# design.net
KiCad netlist of a schematic drawn in Altium Designer
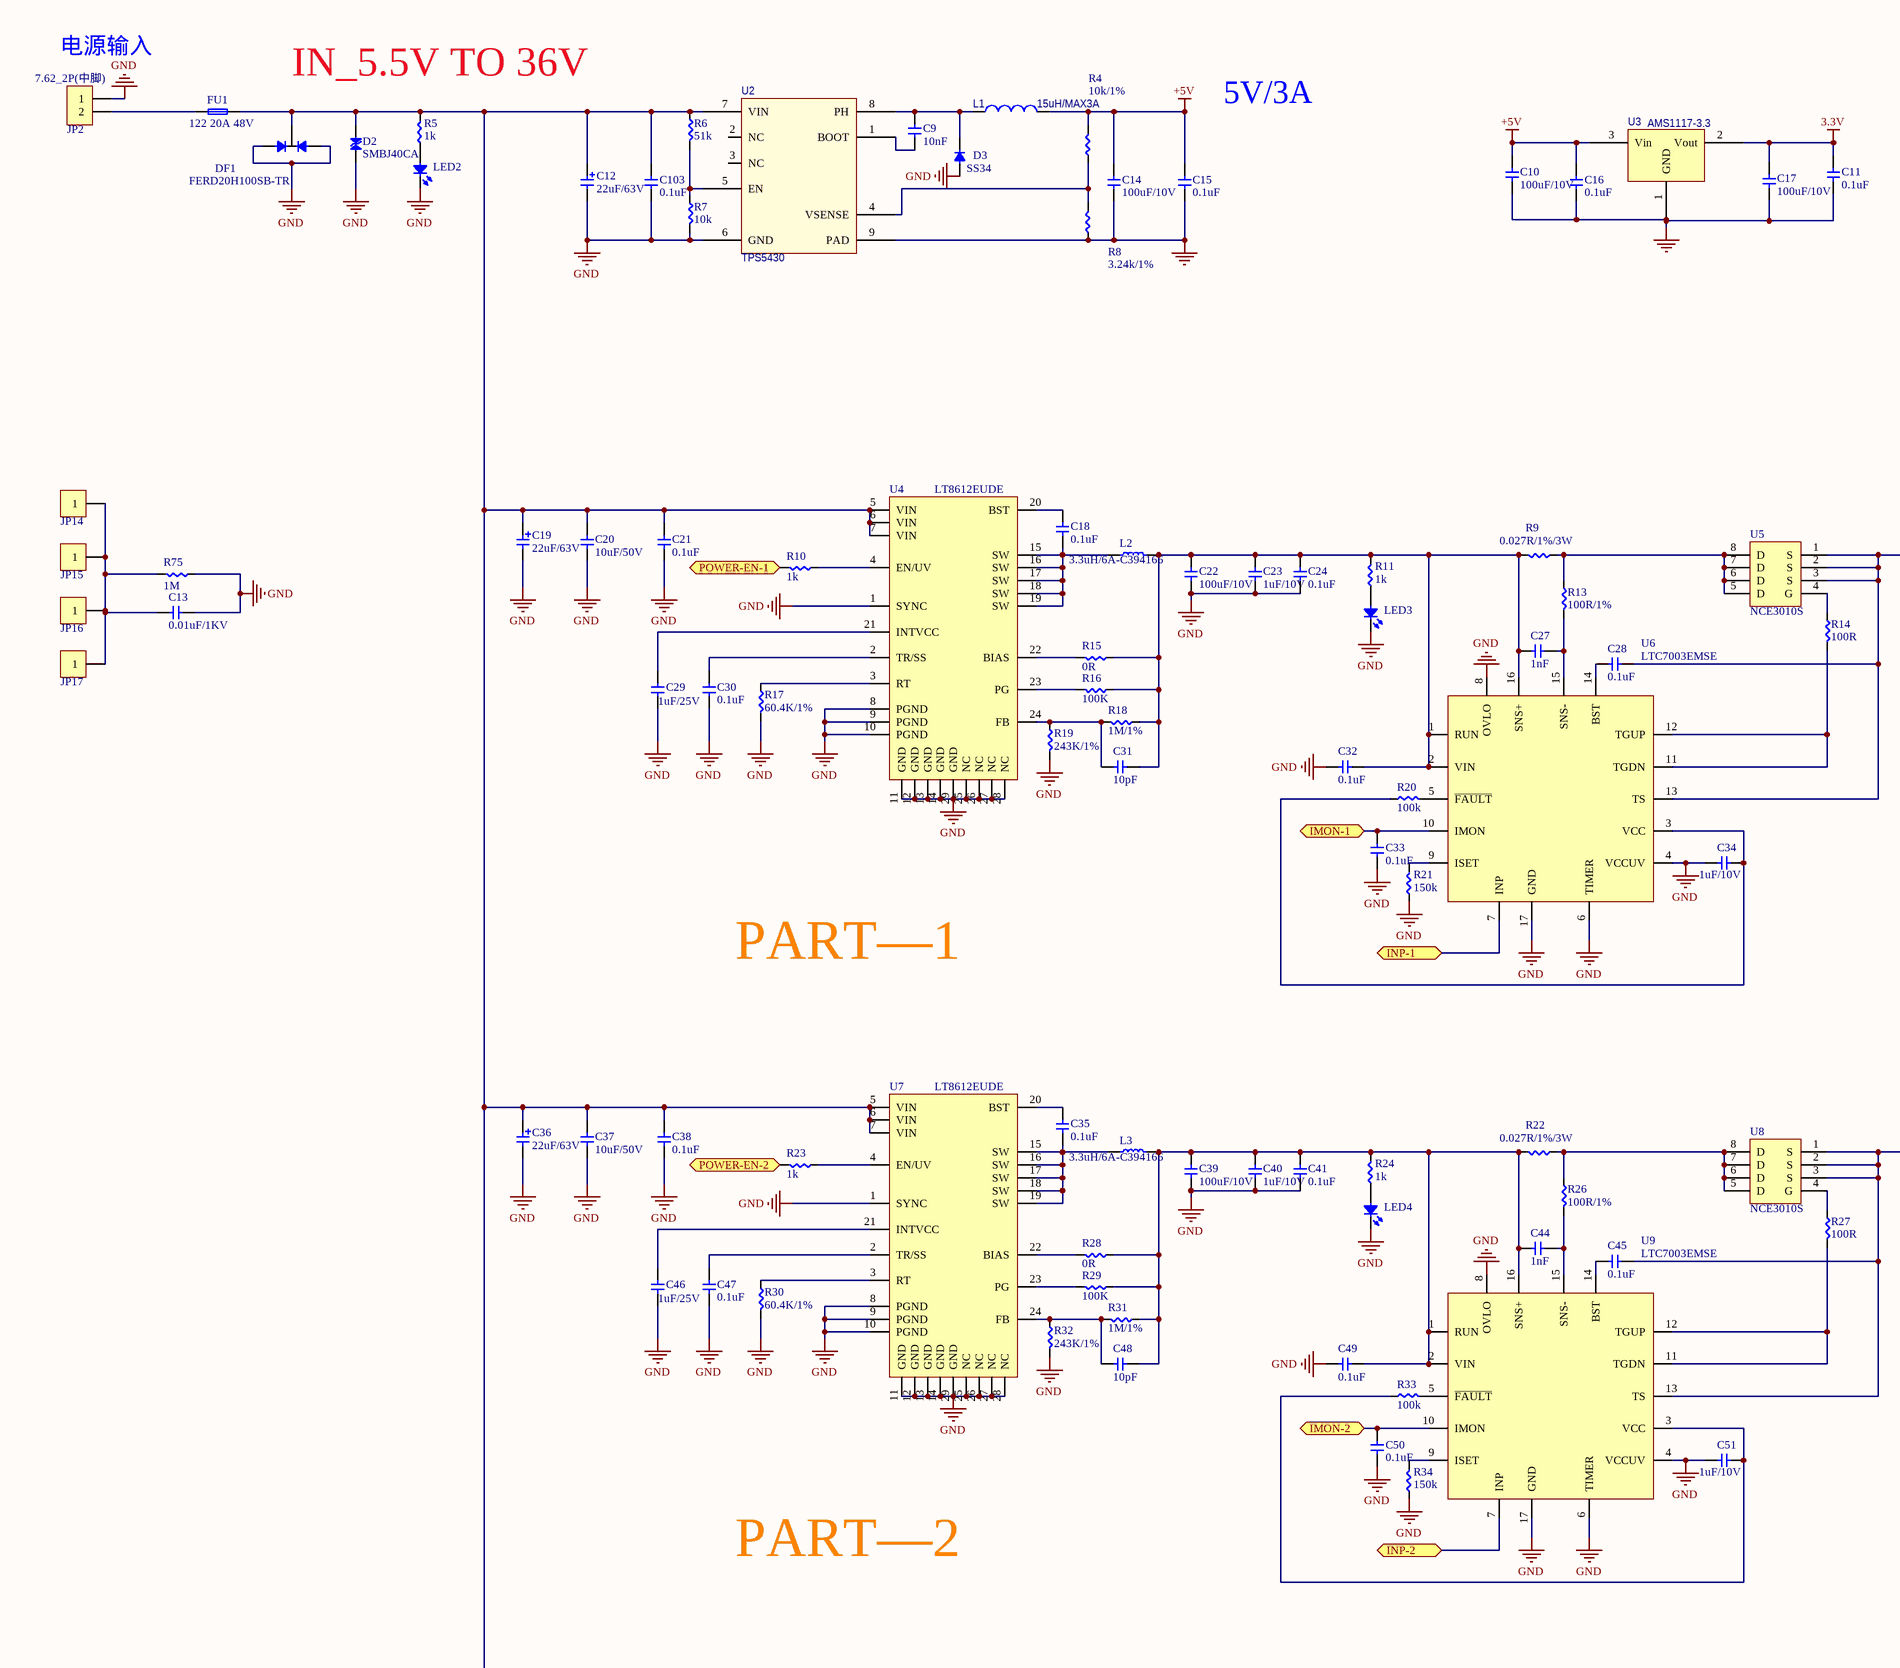
[diagram p0: 电源通道电路.SchDoc, top left]
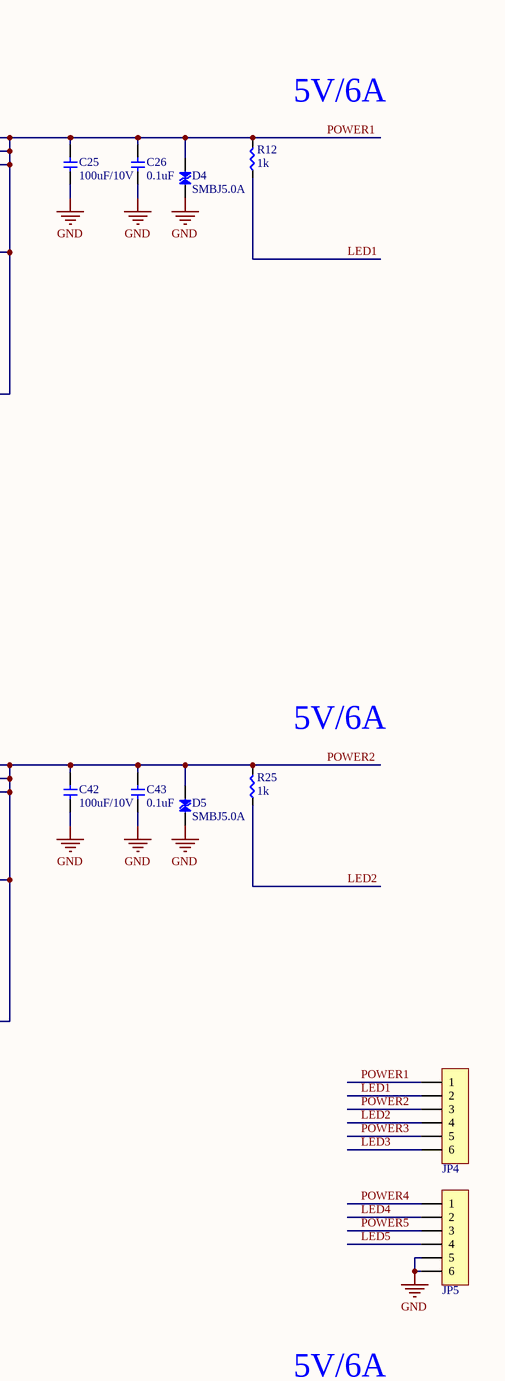
[diagram p1: 电源通道电路.SchDoc, top right]
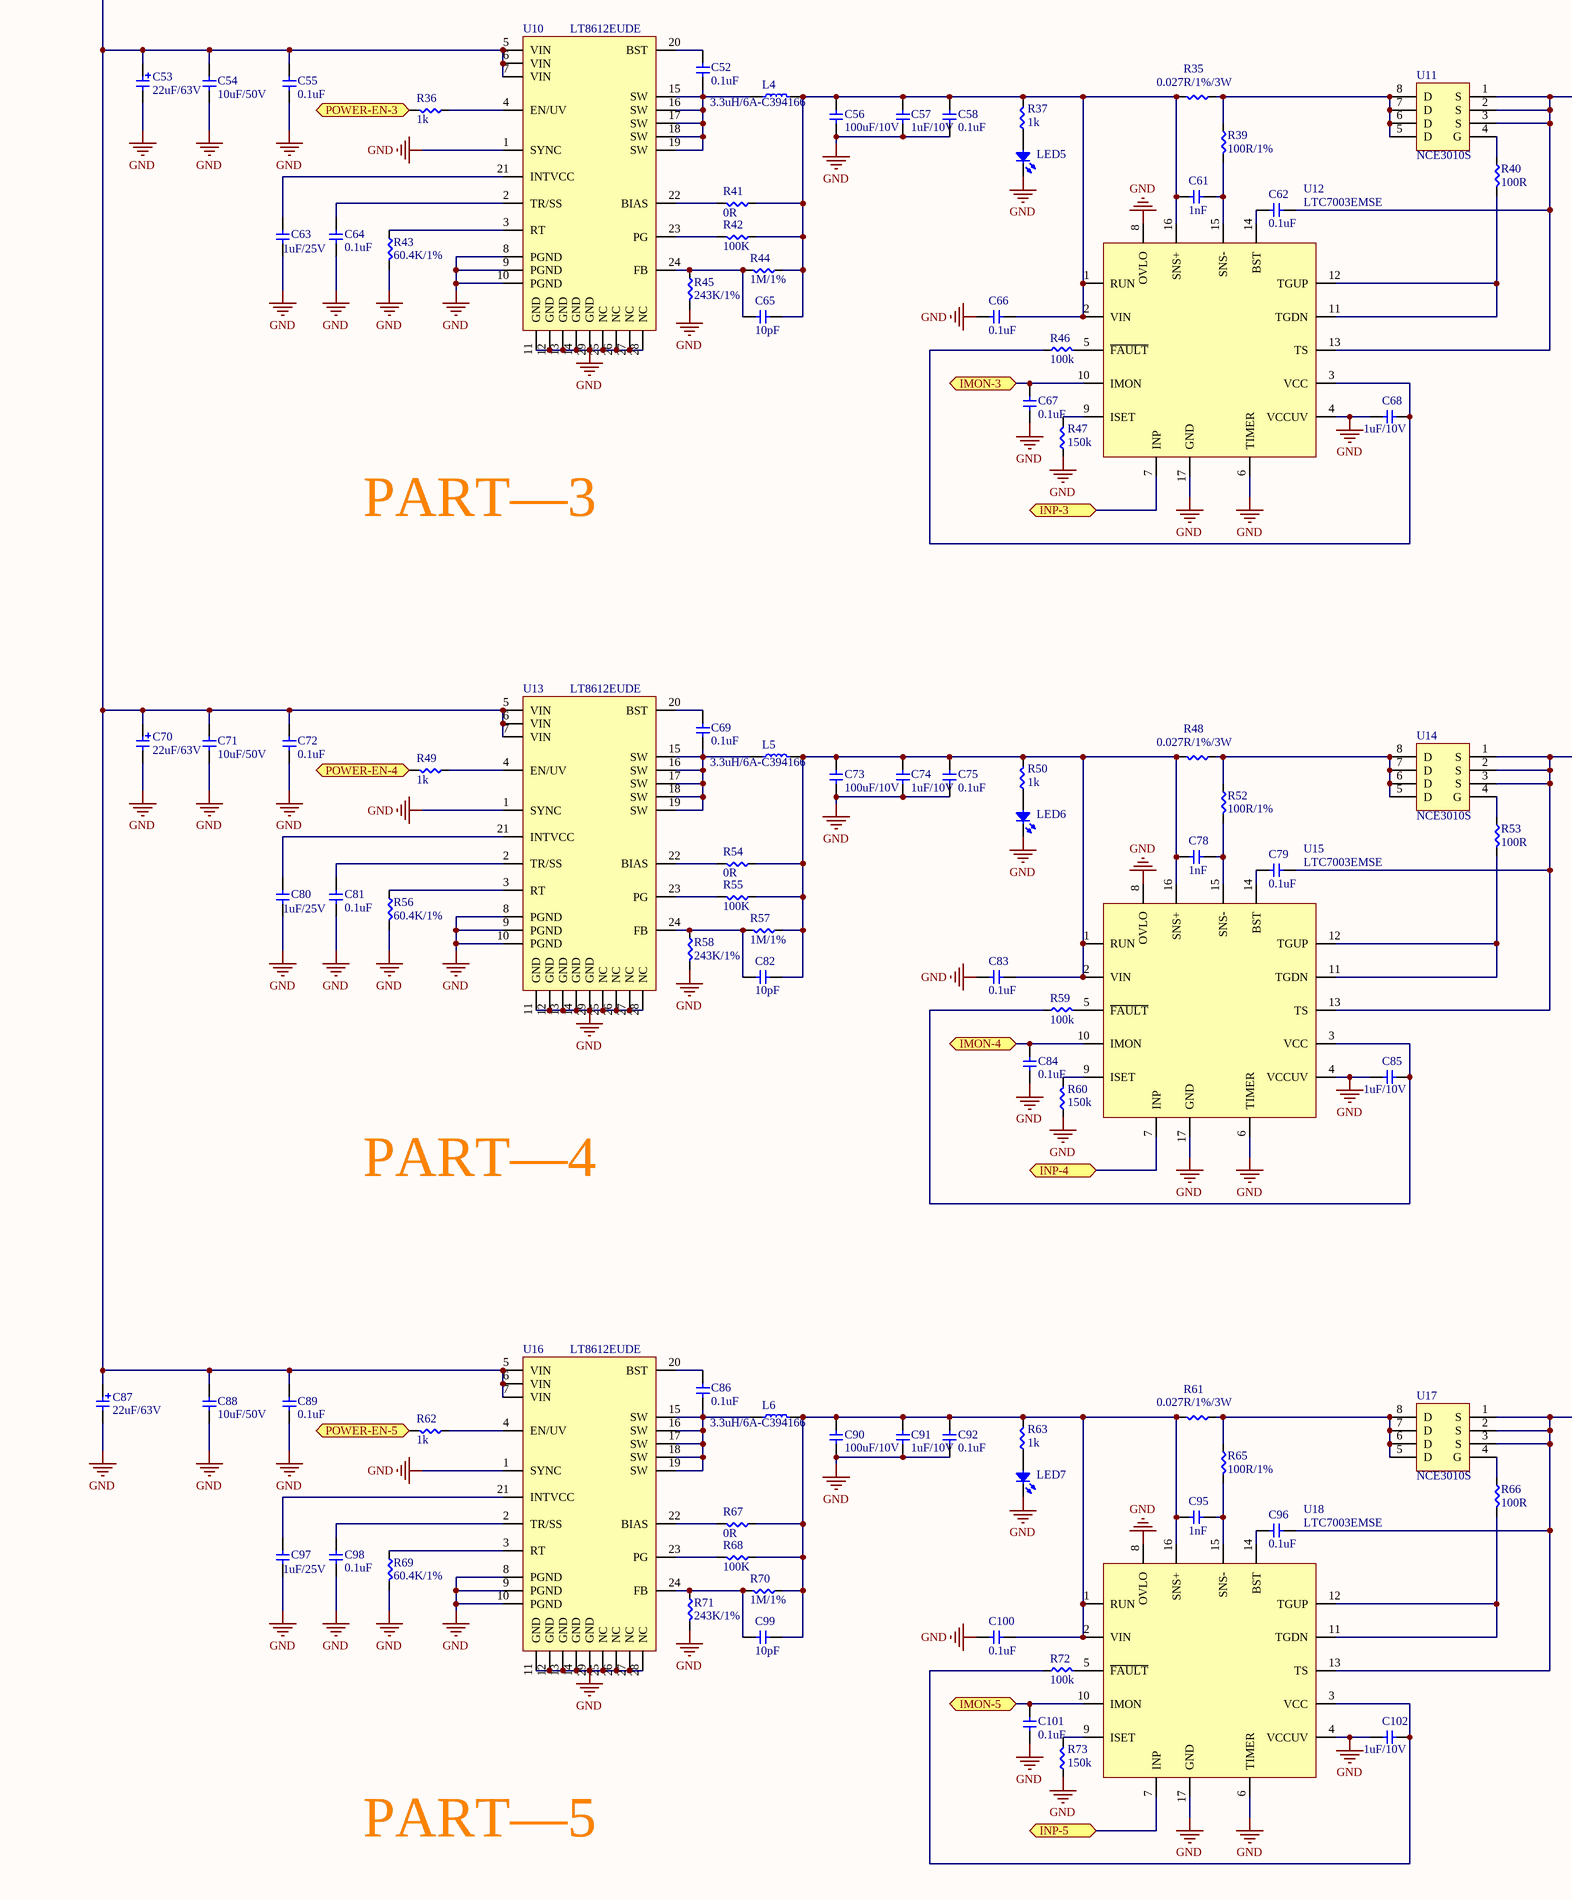
[diagram p2: 电源通道电路.SchDoc, bottom left]
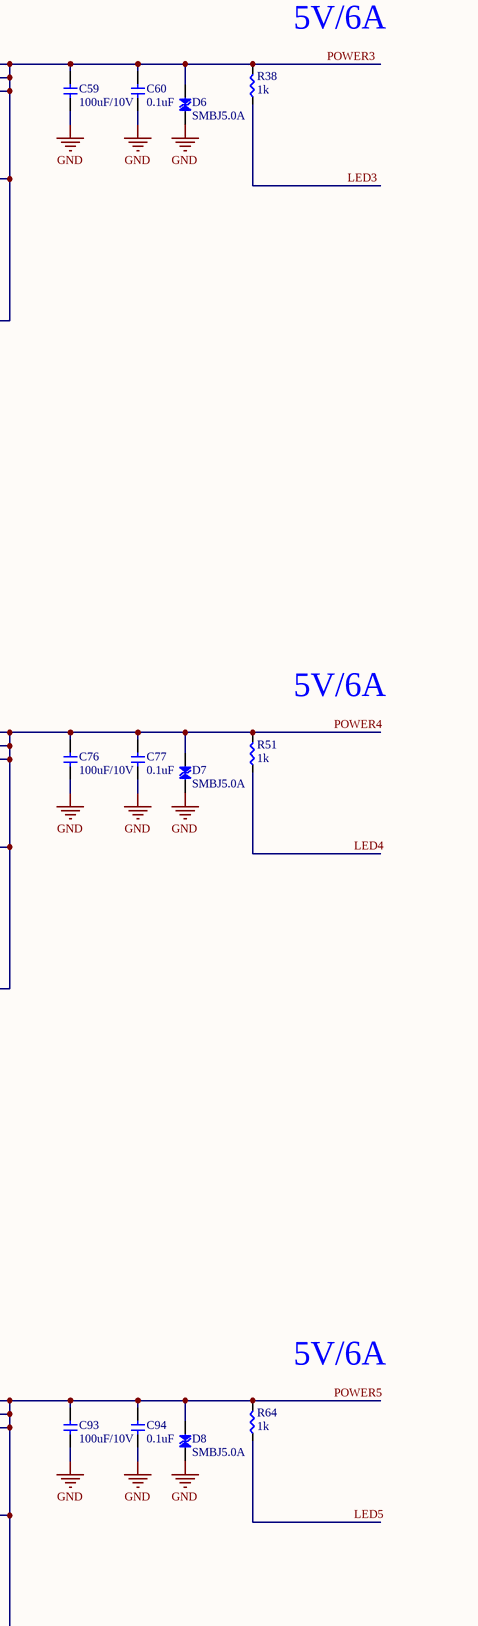
[diagram p3: 电源通道电路.SchDoc, bottom right]

(export (version "E")
  (design (tool "Eeschema 10.0.6"))
  (components
    (comp (ref "C9") (value "10nF") (footprint "C 0603_M") (libsource (lib "史福祥库") (part "C")))
    (comp (ref "C10") (value "100uF/10V") (footprint "CT 5*6 - R") (libsource (lib "史福祥库") (part "C")))
    (comp (ref "C11") (value "0.1uF") (footprint "C 0603_M") (libsource (lib "史福祥库") (part "C")))
    (comp (ref "C12")
      (value "22uF/63V")
      (footprint "CT 8*7 - C")
      (fields (field (name "PUBLISHER") "Altium Limited"))
      (libsource (lib "史福祥库") (part "C+"))
    )
    (comp (ref "C13") (value "0.01uF/1KV") (footprint "C 1210_M") (libsource (lib "史福祥库") (part "C")))
    (comp (ref "C14") (value "100uF/10V") (footprint "CT 5*6 - R") (libsource (lib "史福祥库") (part "C")))
    (comp (ref "C15") (value "0.1uF") (footprint "C 0603_M") (libsource (lib "史福祥库") (part "C")))
    (comp (ref "C16") (value "0.1uF") (footprint "C 0603_M") (libsource (lib "史福祥库") (part "C")))
    (comp (ref "C17") (value "100uF/10V") (footprint "CT 5*6 - R") (libsource (lib "史福祥库") (part "C")))
    (comp (ref "C18") (value "0.1uF") (footprint "C 0603_M") (libsource (lib "史福祥库") (part "C")))
    (comp (ref "C19")
      (value "22uF/63V")
      (footprint "CT 8*7 - C")
      (fields (field (name "PUBLISHER") "Altium Limited"))
      (libsource (lib "史福祥库") (part "C+"))
    )
    (comp (ref "C20") (value "10uF/50V") (footprint "C 1206_M") (libsource (lib "史福祥库") (part "C")))
    (comp (ref "C21") (value "0.1uF") (footprint "C 0603_M") (libsource (lib "史福祥库") (part "C")))
    (comp (ref "C22") (value "100uF/10V") (footprint "CT 5*6 - R") (libsource (lib "史福祥库") (part "C")))
    (comp (ref "C23") (value "1uF/10V") (footprint "C 0603_M") (libsource (lib "史福祥库") (part "C")))
    (comp (ref "C24") (value "0.1uF") (footprint "C 0603_M") (libsource (lib "史福祥库") (part "C")))
    (comp (ref "C25") (value "100uF/10V") (footprint "CT 5*6 - R") (libsource (lib "史福祥库") (part "C")))
    (comp (ref "C26") (value "0.1uF") (footprint "C 0603_M") (libsource (lib "史福祥库") (part "C")))
    (comp (ref "C27") (value "1nF") (footprint "C 0603_M") (libsource (lib "史福祥库") (part "C")))
    (comp (ref "C28") (value "0.1uF") (footprint "C 0603_M") (libsource (lib "史福祥库") (part "C")))
    (comp (ref "C29") (value "1uF/25V") (footprint "C 0603_M") (libsource (lib "史福祥库") (part "C")))
    (comp (ref "C30") (value "0.1uF") (footprint "C 0603_M") (libsource (lib "史福祥库") (part "C")))
    (comp (ref "C31") (value "10pF") (footprint "C 0603_M") (libsource (lib "史福祥库") (part "C")))
    (comp (ref "C32") (value "0.1uF") (footprint "C 0603_M") (libsource (lib "史福祥库") (part "C")))
    (comp (ref "C33") (value "0.1uF") (footprint "C 0603_M") (libsource (lib "史福祥库") (part "C")))
    (comp (ref "C34") (value "1uF/10V") (footprint "C 0603_M") (libsource (lib "史福祥库") (part "C")))
    (comp (ref "C35") (value "0.1uF") (footprint "C 0603_M") (libsource (lib "史福祥库") (part "C")))
    (comp (ref "C36")
      (value "22uF/63V")
      (footprint "CT 8*7 - C")
      (fields (field (name "PUBLISHER") "Altium Limited"))
      (libsource (lib "史福祥库") (part "C+"))
    )
    (comp (ref "C37") (value "10uF/50V") (footprint "C 1206_M") (libsource (lib "史福祥库") (part "C")))
    (comp (ref "C38") (value "0.1uF") (footprint "C 0603_M") (libsource (lib "史福祥库") (part "C")))
    (comp (ref "C39") (value "100uF/10V") (footprint "CT 5*6 - R") (libsource (lib "史福祥库") (part "C")))
    (comp (ref "C40") (value "1uF/10V") (footprint "C 0603_M") (libsource (lib "史福祥库") (part "C")))
    (comp (ref "C41") (value "0.1uF") (footprint "C 0603_M") (libsource (lib "史福祥库") (part "C")))
    (comp (ref "C42") (value "100uF/10V") (footprint "CT 5*6 - R") (libsource (lib "史福祥库") (part "C")))
    (comp (ref "C43") (value "0.1uF") (footprint "C 0603_M") (libsource (lib "史福祥库") (part "C")))
    (comp (ref "C44") (value "1nF") (footprint "C 0603_M") (libsource (lib "史福祥库") (part "C")))
    (comp (ref "C45") (value "0.1uF") (footprint "C 0603_M") (libsource (lib "史福祥库") (part "C")))
    (comp (ref "C46") (value "1uF/25V") (footprint "C 0603_M") (libsource (lib "史福祥库") (part "C")))
    (comp (ref "C47") (value "0.1uF") (footprint "C 0603_M") (libsource (lib "史福祥库") (part "C")))
    (comp (ref "C48") (value "10pF") (footprint "C 0603_M") (libsource (lib "史福祥库") (part "C")))
    (comp (ref "C49") (value "0.1uF") (footprint "C 0603_M") (libsource (lib "史福祥库") (part "C")))
    (comp (ref "C50") (value "0.1uF") (footprint "C 0603_M") (libsource (lib "史福祥库") (part "C")))
    (comp (ref "C51") (value "1uF/10V") (footprint "C 0603_M") (libsource (lib "史福祥库") (part "C")))
    (comp (ref "C52") (value "0.1uF") (footprint "C 0603_M") (libsource (lib "史福祥库") (part "C")))
    (comp (ref "C53")
      (value "22uF/63V")
      (footprint "CT 8*7 - C")
      (fields (field (name "PUBLISHER") "Altium Limited"))
      (libsource (lib "史福祥库") (part "C+"))
    )
    (comp (ref "C54") (value "10uF/50V") (footprint "C 1206_M") (libsource (lib "史福祥库") (part "C")))
    (comp (ref "C55") (value "0.1uF") (footprint "C 0603_M") (libsource (lib "史福祥库") (part "C")))
    (comp (ref "C56") (value "100uF/10V") (footprint "CT 5*6 - R") (libsource (lib "史福祥库") (part "C")))
    (comp (ref "C57") (value "1uF/10V") (footprint "C 0603_M") (libsource (lib "史福祥库") (part "C")))
    (comp (ref "C58") (value "0.1uF") (footprint "C 0603_M") (libsource (lib "史福祥库") (part "C")))
    (comp (ref "C59") (value "100uF/10V") (footprint "CT 5*6 - R") (libsource (lib "史福祥库") (part "C")))
    (comp (ref "C60") (value "0.1uF") (footprint "C 0603_M") (libsource (lib "史福祥库") (part "C")))
    (comp (ref "C61") (value "1nF") (footprint "C 0603_M") (libsource (lib "史福祥库") (part "C")))
    (comp (ref "C62") (value "0.1uF") (footprint "C 0603_M") (libsource (lib "史福祥库") (part "C")))
    (comp (ref "C63") (value "1uF/25V") (footprint "C 0603_M") (libsource (lib "史福祥库") (part "C")))
    (comp (ref "C64") (value "0.1uF") (footprint "C 0603_M") (libsource (lib "史福祥库") (part "C")))
    (comp (ref "C65") (value "10pF") (footprint "C 0603_M") (libsource (lib "史福祥库") (part "C")))
    (comp (ref "C66") (value "0.1uF") (footprint "C 0603_M") (libsource (lib "史福祥库") (part "C")))
    (comp (ref "C67") (value "0.1uF") (footprint "C 0603_M") (libsource (lib "史福祥库") (part "C")))
    (comp (ref "C68") (value "1uF/10V") (footprint "C 0603_M") (libsource (lib "史福祥库") (part "C")))
    (comp (ref "C69") (value "0.1uF") (footprint "C 0603_M") (libsource (lib "史福祥库") (part "C")))
    (comp (ref "C70")
      (value "22uF/63V")
      (footprint "CT 8*7 - C")
      (fields (field (name "PUBLISHER") "Altium Limited"))
      (libsource (lib "史福祥库") (part "C+"))
    )
    (comp (ref "C71") (value "10uF/50V") (footprint "C 1206_M") (libsource (lib "史福祥库") (part "C")))
    (comp (ref "C72") (value "0.1uF") (footprint "C 0603_M") (libsource (lib "史福祥库") (part "C")))
    (comp (ref "C73") (value "100uF/10V") (footprint "CT 5*6 - R") (libsource (lib "史福祥库") (part "C")))
    (comp (ref "C74") (value "1uF/10V") (footprint "C 0603_M") (libsource (lib "史福祥库") (part "C")))
    (comp (ref "C75") (value "0.1uF") (footprint "C 0603_M") (libsource (lib "史福祥库") (part "C")))
    (comp (ref "C76") (value "100uF/10V") (footprint "CT 5*6 - R") (libsource (lib "史福祥库") (part "C")))
    (comp (ref "C77") (value "0.1uF") (footprint "C 0603_M") (libsource (lib "史福祥库") (part "C")))
    (comp (ref "C78") (value "1nF") (footprint "C 0603_M") (libsource (lib "史福祥库") (part "C")))
    (comp (ref "C79") (value "0.1uF") (footprint "C 0603_M") (libsource (lib "史福祥库") (part "C")))
    (comp (ref "C80") (value "1uF/25V") (footprint "C 0603_M") (libsource (lib "史福祥库") (part "C")))
    (comp (ref "C81") (value "0.1uF") (footprint "C 0603_M") (libsource (lib "史福祥库") (part "C")))
    (comp (ref "C82") (value "10pF") (footprint "C 0603_M") (libsource (lib "史福祥库") (part "C")))
    (comp (ref "C83") (value "0.1uF") (footprint "C 0603_M") (libsource (lib "史福祥库") (part "C")))
    (comp (ref "C84") (value "0.1uF") (footprint "C 0603_M") (libsource (lib "史福祥库") (part "C")))
    (comp (ref "C85") (value "1uF/10V") (footprint "C 0603_M") (libsource (lib "史福祥库") (part "C")))
    (comp (ref "C86") (value "0.1uF") (footprint "C 0603_M") (libsource (lib "史福祥库") (part "C")))
    (comp (ref "C87")
      (value "22uF/63V")
      (footprint "CT 8*7 - C")
      (fields (field (name "PUBLISHER") "Altium Limited"))
      (libsource (lib "史福祥库") (part "C+"))
    )
    (comp (ref "C88") (value "10uF/50V") (footprint "C 1206_M") (libsource (lib "史福祥库") (part "C")))
    (comp (ref "C89") (value "0.1uF") (footprint "C 0603_M") (libsource (lib "史福祥库") (part "C")))
    (comp (ref "C90") (value "100uF/10V") (footprint "CT 5*6 - R") (libsource (lib "史福祥库") (part "C")))
    (comp (ref "C91") (value "1uF/10V") (footprint "C 0603_M") (libsource (lib "史福祥库") (part "C")))
    (comp (ref "C92") (value "0.1uF") (footprint "C 0603_M") (libsource (lib "史福祥库") (part "C")))
    (comp (ref "C93") (value "100uF/10V") (footprint "CT 5*6 - R") (libsource (lib "史福祥库") (part "C")))
    (comp (ref "C94") (value "0.1uF") (footprint "C 0603_M") (libsource (lib "史福祥库") (part "C")))
    (comp (ref "C95") (value "1nF") (footprint "C 0603_M") (libsource (lib "史福祥库") (part "C")))
    (comp (ref "C96") (value "0.1uF") (footprint "C 0603_M") (libsource (lib "史福祥库") (part "C")))
    (comp (ref "C97") (value "1uF/25V") (footprint "C 0603_M") (libsource (lib "史福祥库") (part "C")))
    (comp (ref "C98") (value "0.1uF") (footprint "C 0603_M") (libsource (lib "史福祥库") (part "C")))
    (comp (ref "C99") (value "10pF") (footprint "C 0603_M") (libsource (lib "史福祥库") (part "C")))
    (comp (ref "C100") (value "0.1uF") (footprint "C 0603_M") (libsource (lib "史福祥库") (part "C")))
    (comp (ref "C101") (value "0.1uF") (footprint "C 0603_M") (libsource (lib "史福祥库") (part "C")))
    (comp (ref "C102") (value "1uF/10V") (footprint "C 0603_M") (libsource (lib "史福祥库") (part "C")))
    (comp (ref "C103") (value "0.1uF") (footprint "C 0603_M") (libsource (lib "史福祥库") (part "C")))
    (comp (ref "D2")
      (value "SMBJ40CA")
      (footprint "SMB - TVS")
      (fields (field (name "PUBLISHER") "Altium Limited"))
      (libsource (lib "史福祥库") (part "D  TVS"))
    )
    (comp (ref "D3")
      (value "SS34")
      (footprint "SMA")
      (fields (field (name "PUBLISHER") "Altium Limited"))
      (libsource (lib "史福祥库") (part "D"))
    )
    (comp (ref "D4")
      (value "SMBJ5.0A")
      (footprint "SMB - TVS")
      (fields (field (name "PUBLISHER") "Altium Limited"))
      (libsource (lib "史福祥库") (part "D  TVS"))
    )
    (comp (ref "D5")
      (value "SMBJ5.0A")
      (footprint "SMB - TVS")
      (fields (field (name "PUBLISHER") "Altium Limited"))
      (libsource (lib "史福祥库") (part "D  TVS"))
    )
    (comp (ref "D6")
      (value "SMBJ5.0A")
      (footprint "SMB - TVS")
      (fields (field (name "PUBLISHER") "Altium Limited"))
      (libsource (lib "史福祥库") (part "D  TVS"))
    )
    (comp (ref "D7")
      (value "SMBJ5.0A")
      (footprint "SMB - TVS")
      (fields (field (name "PUBLISHER") "Altium Limited"))
      (libsource (lib "史福祥库") (part "D  TVS"))
    )
    (comp (ref "D8")
      (value "SMBJ5.0A")
      (footprint "SMB - TVS")
      (fields (field (name "PUBLISHER") "Altium Limited"))
      (libsource (lib "史福祥库") (part "D  TVS"))
    )
    (comp (ref "DF1")
      (value "FERD20H100SB-TR")
      (footprint "DPAK_FERD20H100SB-TR")
      (libsource (lib "史福祥库") (part "D复合二极管"))
    )
    (comp (ref "FU1") (value "122 20A 48V") (footprint "R 1206_M") (libsource (lib "史福祥库") (part "FUSE")))
    (comp (ref "JP2")
      (value "7.62_2P(中脚)")
      (footprint "7.62_2P(中脚)")
      (description "2P接插件")
      (fields (field (name "版权归属") "源创客"))
      (libsource (lib "4.3   - 接插件-脚距1.5") (part "Header 2"))
    )
    (comp (ref "JP4")
      (value "HDR-1X6")
      (footprint "7.62_6P(中脚)")
      (description "6P接插件")
      (fields (field (name "版权归属") "源创客"))
      (libsource (lib "4.4   - 接插件-脚距2.0") (part "Header 6"))
    )
    (comp (ref "JP5")
      (value "HDR-1X6")
      (footprint "7.62_6P(中脚)")
      (description "6P接插件")
      (fields (field (name "版权归属") "源创客"))
      (libsource (lib "4.4   - 接插件-脚距2.0") (part "Header 6"))
    )
    (comp (ref "JP14")
      (value "冷压插片")
      (footprint "M3 125X300")
      (fields (field (name "版权归属") "源创客"))
      (libsource (lib "4.13 - 接插件-未分类") (part "冷压插片"))
    )
    (comp (ref "JP15")
      (value "冷压插片")
      (footprint "M3 125X300")
      (fields (field (name "版权归属") "源创客"))
      (libsource (lib "4.13 - 接插件-未分类") (part "冷压插片"))
    )
    (comp (ref "JP16")
      (value "冷压插片")
      (footprint "M3 125X300")
      (fields (field (name "版权归属") "源创客"))
      (libsource (lib "4.13 - 接插件-未分类") (part "冷压插片"))
    )
    (comp (ref "JP17")
      (value "冷压插片")
      (footprint "M3 125X300")
      (fields (field (name "版权归属") "源创客"))
      (libsource (lib "4.13 - 接插件-未分类") (part "冷压插片"))
    )
    (comp (ref "L1") (value "15uH/MAX3A") (footprint "CDRH74") (libsource (lib "*") (part "INDUCTOR")))
    (comp (ref "L2")
      (value "3.3uH/6A-C394166")
      (footprint "7045")
      (fields (field (name "PUBLISHER") "Altium Limited"))
      (libsource (lib "史福祥库") (part "L"))
    )
    (comp (ref "L3")
      (value "3.3uH/6A-C394166")
      (footprint "7045")
      (fields (field (name "PUBLISHER") "Altium Limited"))
      (libsource (lib "史福祥库") (part "L"))
    )
    (comp (ref "L4")
      (value "3.3uH/6A-C394166")
      (footprint "7045")
      (fields (field (name "PUBLISHER") "Altium Limited"))
      (libsource (lib "史福祥库") (part "L"))
    )
    (comp (ref "L5")
      (value "3.3uH/6A-C394166")
      (footprint "7045")
      (fields (field (name "PUBLISHER") "Altium Limited"))
      (libsource (lib "史福祥库") (part "L"))
    )
    (comp (ref "L6")
      (value "3.3uH/6A-C394166")
      (footprint "7045")
      (fields (field (name "PUBLISHER") "Altium Limited"))
      (libsource (lib "史福祥库") (part "L"))
    )
    (comp (ref "LED2")
      (value "LED")
      (footprint "LED 0603G")
      (fields (field (name "PUBLISHER") "Altium Limited"))
      (libsource (lib "史福祥库") (part "LED"))
    )
    (comp (ref "LED3")
      (value "LED")
      (footprint "LED 0603G")
      (fields (field (name "PUBLISHER") "Altium Limited"))
      (libsource (lib "史福祥库") (part "LED"))
    )
    (comp (ref "LED4")
      (value "LED")
      (footprint "LED 0603G")
      (fields (field (name "PUBLISHER") "Altium Limited"))
      (libsource (lib "史福祥库") (part "LED"))
    )
    (comp (ref "LED5")
      (value "LED")
      (footprint "LED 0603G")
      (fields (field (name "PUBLISHER") "Altium Limited"))
      (libsource (lib "史福祥库") (part "LED"))
    )
    (comp (ref "LED6")
      (value "LED")
      (footprint "LED 0603G")
      (fields (field (name "PUBLISHER") "Altium Limited"))
      (libsource (lib "史福祥库") (part "LED"))
    )
    (comp (ref "LED7")
      (value "LED")
      (footprint "LED 0603G")
      (fields (field (name "PUBLISHER") "Altium Limited"))
      (libsource (lib "史福祥库") (part "LED"))
    )
    (comp (ref "R4") (value "10k/1%") (footprint "R 0603_M") (libsource (lib "史福祥库") (part "Res")))
    (comp (ref "R5") (value "1k") (footprint "R 0603_M") (libsource (lib "史福祥库") (part "Res")))
    (comp (ref "R6") (value "51k") (footprint "R 0603_M") (libsource (lib "史福祥库") (part "Res")))
    (comp (ref "R7") (value "10k") (footprint "R 0603_M") (libsource (lib "史福祥库") (part "Res")))
    (comp (ref "R8") (value "3.24k/1%") (footprint "R 0603_M") (libsource (lib "史福祥库") (part "Res")))
    (comp (ref "R9") (value "0.027R/1%/3W") (footprint "R 2512_M") (libsource (lib "史福祥库") (part "Res")))
    (comp (ref "R10") (value "1k") (footprint "R 0603_M") (libsource (lib "史福祥库") (part "Res")))
    (comp (ref "R11") (value "1k") (footprint "R 0603_M") (libsource (lib "史福祥库") (part "Res")))
    (comp (ref "R12") (value "1k") (footprint "R 0603_M") (libsource (lib "史福祥库") (part "Res")))
    (comp (ref "R13") (value "100R/1%") (footprint "R 0603_M") (libsource (lib "史福祥库") (part "Res")))
    (comp (ref "R14") (value "100R") (footprint "R 0603_M") (libsource (lib "史福祥库") (part "Res")))
    (comp (ref "R15") (value "0R") (footprint "R 0603_M") (libsource (lib "史福祥库") (part "Res")))
    (comp (ref "R16") (value "100K") (footprint "R 0603_M") (libsource (lib "史福祥库") (part "Res")))
    (comp (ref "R17") (value "60.4K/1%") (footprint "R 0603_M") (libsource (lib "史福祥库") (part "Res")))
    (comp (ref "R18") (value "1M/1%") (footprint "R 0603_M") (libsource (lib "史福祥库") (part "Res")))
    (comp (ref "R19") (value "243K/1%") (footprint "R 0603_M") (libsource (lib "史福祥库") (part "Res")))
    (comp (ref "R20") (value "100k") (footprint "R 0603_M") (libsource (lib "史福祥库") (part "Res")))
    (comp (ref "R21") (value "150k") (footprint "R 0603_M") (libsource (lib "史福祥库") (part "Res")))
    (comp (ref "R22") (value "0.027R/1%/3W") (footprint "R 2512_M") (libsource (lib "史福祥库") (part "Res")))
    (comp (ref "R23") (value "1k") (footprint "R 0603_M") (libsource (lib "史福祥库") (part "Res")))
    (comp (ref "R24") (value "1k") (footprint "R 0603_M") (libsource (lib "史福祥库") (part "Res")))
    (comp (ref "R25") (value "1k") (footprint "R 0603_M") (libsource (lib "史福祥库") (part "Res")))
    (comp (ref "R26") (value "100R/1%") (footprint "R 0603_M") (libsource (lib "史福祥库") (part "Res")))
    (comp (ref "R27") (value "100R") (footprint "R 0603_M") (libsource (lib "史福祥库") (part "Res")))
    (comp (ref "R28") (value "0R") (footprint "R 0603_M") (libsource (lib "史福祥库") (part "Res")))
    (comp (ref "R29") (value "100K") (footprint "R 0603_M") (libsource (lib "史福祥库") (part "Res")))
    (comp (ref "R30") (value "60.4K/1%") (footprint "R 0603_M") (libsource (lib "史福祥库") (part "Res")))
    (comp (ref "R31") (value "1M/1%") (footprint "R 0603_M") (libsource (lib "史福祥库") (part "Res")))
    (comp (ref "R32") (value "243K/1%") (footprint "R 0603_M") (libsource (lib "史福祥库") (part "Res")))
    (comp (ref "R33") (value "100k") (footprint "R 0603_M") (libsource (lib "史福祥库") (part "Res")))
    (comp (ref "R34") (value "150k") (footprint "R 0603_M") (libsource (lib "史福祥库") (part "Res")))
    (comp (ref "R35") (value "0.027R/1%/3W") (footprint "R 2512_M") (libsource (lib "史福祥库") (part "Res")))
    (comp (ref "R36") (value "1k") (footprint "R 0603_M") (libsource (lib "史福祥库") (part "Res")))
    (comp (ref "R37") (value "1k") (footprint "R 0603_M") (libsource (lib "史福祥库") (part "Res")))
    (comp (ref "R38") (value "1k") (footprint "R 0603_M") (libsource (lib "史福祥库") (part "Res")))
    (comp (ref "R39") (value "100R/1%") (footprint "R 0603_M") (libsource (lib "史福祥库") (part "Res")))
    (comp (ref "R40") (value "100R") (footprint "R 0603_M") (libsource (lib "史福祥库") (part "Res")))
    (comp (ref "R41") (value "0R") (footprint "R 0603_M") (libsource (lib "史福祥库") (part "Res")))
    (comp (ref "R42") (value "100K") (footprint "R 0603_M") (libsource (lib "史福祥库") (part "Res")))
    (comp (ref "R43") (value "60.4K/1%") (footprint "R 0603_M") (libsource (lib "史福祥库") (part "Res")))
    (comp (ref "R44") (value "1M/1%") (footprint "R 0603_M") (libsource (lib "史福祥库") (part "Res")))
    (comp (ref "R45") (value "243K/1%") (footprint "R 0603_M") (libsource (lib "史福祥库") (part "Res")))
    (comp (ref "R46") (value "100k") (footprint "R 0603_M") (libsource (lib "史福祥库") (part "Res")))
    (comp (ref "R47") (value "150k") (footprint "R 0603_M") (libsource (lib "史福祥库") (part "Res")))
    (comp (ref "R48") (value "0.027R/1%/3W") (footprint "R 2512_M") (libsource (lib "史福祥库") (part "Res")))
    (comp (ref "R49") (value "1k") (footprint "R 0603_M") (libsource (lib "史福祥库") (part "Res")))
    (comp (ref "R50") (value "1k") (footprint "R 0603_M") (libsource (lib "史福祥库") (part "Res")))
    (comp (ref "R51") (value "1k") (footprint "R 0603_M") (libsource (lib "史福祥库") (part "Res")))
    (comp (ref "R52") (value "100R/1%") (footprint "R 0603_M") (libsource (lib "史福祥库") (part "Res")))
    (comp (ref "R53") (value "100R") (footprint "R 0603_M") (libsource (lib "史福祥库") (part "Res")))
    (comp (ref "R54") (value "0R") (footprint "R 0603_M") (libsource (lib "史福祥库") (part "Res")))
    (comp (ref "R55") (value "100K") (footprint "R 0603_M") (libsource (lib "史福祥库") (part "Res")))
    (comp (ref "R56") (value "60.4K/1%") (footprint "R 0603_M") (libsource (lib "史福祥库") (part "Res")))
    (comp (ref "R57") (value "1M/1%") (footprint "R 0603_M") (libsource (lib "史福祥库") (part "Res")))
    (comp (ref "R58") (value "243K/1%") (footprint "R 0603_M") (libsource (lib "史福祥库") (part "Res")))
    (comp (ref "R59") (value "100k") (footprint "R 0603_M") (libsource (lib "史福祥库") (part "Res")))
    (comp (ref "R60") (value "150k") (footprint "R 0603_M") (libsource (lib "史福祥库") (part "Res")))
    (comp (ref "R61") (value "0.027R/1%/3W") (footprint "R 2512_M") (libsource (lib "史福祥库") (part "Res")))
    (comp (ref "R62") (value "1k") (footprint "R 0603_M") (libsource (lib "史福祥库") (part "Res")))
    (comp (ref "R63") (value "1k") (footprint "R 0603_M") (libsource (lib "史福祥库") (part "Res")))
    (comp (ref "R64") (value "1k") (footprint "R 0603_M") (libsource (lib "史福祥库") (part "Res")))
    (comp (ref "R65") (value "100R/1%") (footprint "R 0603_M") (libsource (lib "史福祥库") (part "Res")))
    (comp (ref "R66") (value "100R") (footprint "R 0603_M") (libsource (lib "史福祥库") (part "Res")))
    (comp (ref "R67") (value "0R") (footprint "R 0603_M") (libsource (lib "史福祥库") (part "Res")))
    (comp (ref "R68") (value "100K") (footprint "R 0603_M") (libsource (lib "史福祥库") (part "Res")))
    (comp (ref "R69") (value "60.4K/1%") (footprint "R 0603_M") (libsource (lib "史福祥库") (part "Res")))
    (comp (ref "R70") (value "1M/1%") (footprint "R 0603_M") (libsource (lib "史福祥库") (part "Res")))
    (comp (ref "R71") (value "243K/1%") (footprint "R 0603_M") (libsource (lib "史福祥库") (part "Res")))
    (comp (ref "R72") (value "100k") (footprint "R 0603_M") (libsource (lib "史福祥库") (part "Res")))
    (comp (ref "R73") (value "150k") (footprint "R 0603_M") (libsource (lib "史福祥库") (part "Res")))
    (comp (ref "R75") (value "1M") (footprint "R 0603_M") (libsource (lib "史福祥库") (part "Res")))
    (comp (ref "U2")
      (value "TPS5430")
      (footprint "SOP127P780-9")
      (description "3-A, Wide Input Range, Step-Down Converter")
      (libsource (lib "SCHLIB") (part "TPS5430"))
    )
    (comp (ref "U3")
      (value "AMS1117-3.3")
      (footprint "SOT-223-4")
      (libsource (lib "2800DLFP(C3)") (part "LM1117-33"))
    )
    (comp (ref "U4")
      (value "LT8612EUDE")
      (footprint "QFN-28_LT8612EUDE")
      (libsource (lib "1.3   - 电源类芯片") (part "LT8612EUDE"))
    )
    (comp (ref "U5")
      (value "NCE3010S")
      (footprint "SOP8")
      (libsource (lib "6.1   - 场效应管-可控硅") (part "IRF7240PBF"))
    )
    (comp (ref "U6")
      (value "LTC7003EMSE")
      (footprint "MSOP-16")
      (libsource (lib "1.3   - 电源类芯片") (part "LTC7003EMSE"))
    )
    (comp (ref "U7")
      (value "LT8612EUDE")
      (footprint "QFN-28_LT8612EUDE")
      (libsource (lib "1.3   - 电源类芯片") (part "LT8612EUDE"))
    )
    (comp (ref "U8")
      (value "NCE3010S")
      (footprint "SOP8")
      (libsource (lib "6.1   - 场效应管-可控硅") (part "IRF7240PBF"))
    )
    (comp (ref "U9")
      (value "LTC7003EMSE")
      (footprint "MSOP-16")
      (libsource (lib "1.3   - 电源类芯片") (part "LTC7003EMSE"))
    )
    (comp (ref "U10")
      (value "LT8612EUDE")
      (footprint "QFN-28_LT8612EUDE")
      (libsource (lib "1.3   - 电源类芯片") (part "LT8612EUDE"))
    )
    (comp (ref "U11")
      (value "NCE3010S")
      (footprint "SOP8")
      (libsource (lib "6.1   - 场效应管-可控硅") (part "IRF7240PBF"))
    )
    (comp (ref "U12")
      (value "LTC7003EMSE")
      (footprint "MSOP-16")
      (libsource (lib "1.3   - 电源类芯片") (part "LTC7003EMSE"))
    )
    (comp (ref "U13")
      (value "LT8612EUDE")
      (footprint "QFN-28_LT8612EUDE")
      (libsource (lib "1.3   - 电源类芯片") (part "LT8612EUDE"))
    )
    (comp (ref "U14")
      (value "NCE3010S")
      (footprint "SOP8")
      (libsource (lib "6.1   - 场效应管-可控硅") (part "IRF7240PBF"))
    )
    (comp (ref "U15")
      (value "LTC7003EMSE")
      (footprint "MSOP-16")
      (libsource (lib "1.3   - 电源类芯片") (part "LTC7003EMSE"))
    )
    (comp (ref "U16")
      (value "LT8612EUDE")
      (footprint "QFN-28_LT8612EUDE")
      (libsource (lib "1.3   - 电源类芯片") (part "LT8612EUDE"))
    )
    (comp (ref "U17")
      (value "NCE3010S")
      (footprint "SOP8")
      (libsource (lib "6.1   - 场效应管-可控硅") (part "IRF7240PBF"))
    )
    (comp (ref "U18")
      (value "LTC7003EMSE")
      (footprint "MSOP-16")
      (libsource (lib "1.3   - 电源类芯片") (part "LTC7003EMSE"))
    )
  )
  (nets
    (net (code "1") (name "+5V") (class "Default")
      (node (ref "C10") (pin "2") (pinfunction "2_2") (pintype "passive"))
      (node (ref "C14") (pin "2") (pinfunction "2_2") (pintype "passive"))
      (node (ref "C15") (pin "2") (pinfunction "2_2") (pintype "passive"))
      (node (ref "C16") (pin "2") (pinfunction "2_2") (pintype "passive"))
      (node (ref "L1") (pin "2") (pinfunction "2_2") (pintype "passive"))
      (node (ref "R4") (pin "2") (pinfunction "2_2") (pintype "passive"))
      (node (ref "U3") (pin "3") (pinfunction "Vin_3") (pintype "passive"))
    )
    (net (code "2") (name "/IMON-1") (class "Default")
      (node (ref "C33") (pin "1") (pinfunction "1_1") (pintype "passive"))
      (node (ref "U6") (pin "10") (pinfunction "IMON_10") (pintype "passive"))
    )
    (net (code "3") (name "/IMON-2") (class "Default")
      (node (ref "C50") (pin "1") (pinfunction "1_1") (pintype "passive"))
      (node (ref "U9") (pin "10") (pinfunction "IMON_10") (pintype "passive"))
    )
    (net (code "4") (name "/IMON-3") (class "Default")
      (node (ref "C67") (pin "1") (pinfunction "1_1") (pintype "passive"))
      (node (ref "U12") (pin "10") (pinfunction "IMON_10") (pintype "passive"))
    )
    (net (code "5") (name "/IMON-4") (class "Default")
      (node (ref "C84") (pin "1") (pinfunction "1_1") (pintype "passive"))
      (node (ref "U15") (pin "10") (pinfunction "IMON_10") (pintype "passive"))
    )
    (net (code "6") (name "/IMON-5") (class "Default")
      (node (ref "C101") (pin "1") (pinfunction "1_1") (pintype "passive"))
      (node (ref "U18") (pin "10") (pinfunction "IMON_10") (pintype "passive"))
    )
    (net (code "7") (name "/INP-1") (class "Default")
      (node (ref "U6") (pin "7") (pinfunction "INP_7") (pintype "passive"))
    )
    (net (code "8") (name "/INP-2") (class "Default")
      (node (ref "U9") (pin "7") (pinfunction "INP_7") (pintype "passive"))
    )
    (net (code "9") (name "/INP-3") (class "Default")
      (node (ref "U12") (pin "7") (pinfunction "INP_7") (pintype "passive"))
    )
    (net (code "10") (name "/INP-4") (class "Default")
      (node (ref "U15") (pin "7") (pinfunction "INP_7") (pintype "passive"))
    )
    (net (code "11") (name "/INP-5") (class "Default")
      (node (ref "U18") (pin "7") (pinfunction "INP_7") (pintype "passive"))
    )
    (net (code "12") (name "/LED1") (class "Default")
      (node (ref "JP4") (pin "2") (pinfunction "2_2") (pintype "passive"))
      (node (ref "R12") (pin "1") (pinfunction "1_1") (pintype "passive"))
    )
    (net (code "13") (name "/LED2") (class "Default")
      (node (ref "JP4") (pin "4") (pinfunction "4_4") (pintype "passive"))
      (node (ref "R25") (pin "1") (pinfunction "1_1") (pintype "passive"))
    )
    (net (code "14") (name "/LED3") (class "Default")
      (node (ref "JP4") (pin "6") (pinfunction "6_6") (pintype "passive"))
      (node (ref "R38") (pin "1") (pinfunction "1_1") (pintype "passive"))
    )
    (net (code "15") (name "/LED4") (class "Default")
      (node (ref "JP5") (pin "2") (pinfunction "2_2") (pintype "passive"))
      (node (ref "R51") (pin "1") (pinfunction "1_1") (pintype "passive"))
    )
    (net (code "16") (name "/LED5") (class "Default")
      (node (ref "JP5") (pin "4") (pinfunction "4_4") (pintype "passive"))
      (node (ref "R64") (pin "1") (pinfunction "1_1") (pintype "passive"))
    )
    (net (code "17") (name "/POWER-EN-1") (class "Default")
      (node (ref "R10") (pin "2") (pinfunction "2_2") (pintype "passive"))
    )
    (net (code "18") (name "/POWER-EN-2") (class "Default")
      (node (ref "R23") (pin "2") (pinfunction "2_2") (pintype "passive"))
    )
    (net (code "19") (name "/POWER-EN-3") (class "Default")
      (node (ref "R36") (pin "2") (pinfunction "2_2") (pintype "passive"))
    )
    (net (code "20") (name "/POWER-EN-4") (class "Default")
      (node (ref "R49") (pin "2") (pinfunction "2_2") (pintype "passive"))
    )
    (net (code "21") (name "/POWER-EN-5") (class "Default")
      (node (ref "R62") (pin "2") (pinfunction "2_2") (pintype "passive"))
    )
    (net (code "22") (name "/POWER1") (class "Default")
      (node (ref "C25") (pin "2") (pinfunction "2_2") (pintype "passive"))
      (node (ref "C26") (pin "2") (pinfunction "2_2") (pintype "passive"))
      (node (ref "C28") (pin "1") (pinfunction "1_1") (pintype "passive"))
      (node (ref "D4") (pin "2") (pinfunction "K_2") (pintype "passive"))
      (node (ref "JP4") (pin "1") (pinfunction "1_1") (pintype "passive"))
      (node (ref "R12") (pin "2") (pinfunction "2_2") (pintype "passive"))
      (node (ref "U5") (pin "1") (pinfunction "S_1") (pintype "passive"))
      (node (ref "U5") (pin "2") (pinfunction "S_2") (pintype "passive"))
      (node (ref "U5") (pin "3") (pinfunction "S_3") (pintype "passive"))
      (node (ref "U6") (pin "13") (pinfunction "TS_13") (pintype "passive"))
    )
    (net (code "23") (name "/POWER2") (class "Default")
      (node (ref "C42") (pin "2") (pinfunction "2_2") (pintype "passive"))
      (node (ref "C43") (pin "2") (pinfunction "2_2") (pintype "passive"))
      (node (ref "C45") (pin "1") (pinfunction "1_1") (pintype "passive"))
      (node (ref "D5") (pin "2") (pinfunction "K_2") (pintype "passive"))
      (node (ref "JP4") (pin "3") (pinfunction "3_3") (pintype "passive"))
      (node (ref "R25") (pin "2") (pinfunction "2_2") (pintype "passive"))
      (node (ref "U8") (pin "1") (pinfunction "S_1") (pintype "passive"))
      (node (ref "U8") (pin "2") (pinfunction "S_2") (pintype "passive"))
      (node (ref "U8") (pin "3") (pinfunction "S_3") (pintype "passive"))
      (node (ref "U9") (pin "13") (pinfunction "TS_13") (pintype "passive"))
    )
    (net (code "24") (name "/POWER3") (class "Default")
      (node (ref "C59") (pin "2") (pinfunction "2_2") (pintype "passive"))
      (node (ref "C60") (pin "2") (pinfunction "2_2") (pintype "passive"))
      (node (ref "C62") (pin "1") (pinfunction "1_1") (pintype "passive"))
      (node (ref "D6") (pin "2") (pinfunction "K_2") (pintype "passive"))
      (node (ref "JP4") (pin "5") (pinfunction "5_5") (pintype "passive"))
      (node (ref "R38") (pin "2") (pinfunction "2_2") (pintype "passive"))
      (node (ref "U11") (pin "1") (pinfunction "S_1") (pintype "passive"))
      (node (ref "U11") (pin "2") (pinfunction "S_2") (pintype "passive"))
      (node (ref "U11") (pin "3") (pinfunction "S_3") (pintype "passive"))
      (node (ref "U12") (pin "13") (pinfunction "TS_13") (pintype "passive"))
    )
    (net (code "25") (name "/POWER4") (class "Default")
      (node (ref "C76") (pin "2") (pinfunction "2_2") (pintype "passive"))
      (node (ref "C77") (pin "2") (pinfunction "2_2") (pintype "passive"))
      (node (ref "C79") (pin "1") (pinfunction "1_1") (pintype "passive"))
      (node (ref "D7") (pin "2") (pinfunction "K_2") (pintype "passive"))
      (node (ref "JP5") (pin "1") (pinfunction "1_1") (pintype "passive"))
      (node (ref "R51") (pin "2") (pinfunction "2_2") (pintype "passive"))
      (node (ref "U14") (pin "1") (pinfunction "S_1") (pintype "passive"))
      (node (ref "U14") (pin "2") (pinfunction "S_2") (pintype "passive"))
      (node (ref "U14") (pin "3") (pinfunction "S_3") (pintype "passive"))
      (node (ref "U15") (pin "13") (pinfunction "TS_13") (pintype "passive"))
    )
    (net (code "26") (name "/POWER5") (class "Default")
      (node (ref "C93") (pin "2") (pinfunction "2_2") (pintype "passive"))
      (node (ref "C94") (pin "2") (pinfunction "2_2") (pintype "passive"))
      (node (ref "C96") (pin "1") (pinfunction "1_1") (pintype "passive"))
      (node (ref "D8") (pin "2") (pinfunction "K_2") (pintype "passive"))
      (node (ref "JP5") (pin "3") (pinfunction "3_3") (pintype "passive"))
      (node (ref "R64") (pin "2") (pinfunction "2_2") (pintype "passive"))
      (node (ref "U17") (pin "1") (pinfunction "S_1") (pintype "passive"))
      (node (ref "U17") (pin "2") (pinfunction "S_2") (pintype "passive"))
      (node (ref "U17") (pin "3") (pinfunction "S_3") (pintype "passive"))
      (node (ref "U18") (pin "13") (pinfunction "TS_13") (pintype "passive"))
    )
    (net (code "27") (name "3.3V") (class "Default")
      (node (ref "C11") (pin "2") (pinfunction "2_2") (pintype "passive"))
      (node (ref "C17") (pin "2") (pinfunction "2_2") (pintype "passive"))
      (node (ref "U3") (pin "2") (pinfunction "Vout_2") (pintype "passive"))
    )
    (net (code "28") (name "GND") (class "Default")
      (node (ref "C10") (pin "1") (pinfunction "1_1") (pintype "passive"))
      (node (ref "C100") (pin "1") (pinfunction "1_1") (pintype "passive"))
      (node (ref "C101") (pin "2") (pinfunction "2_2") (pintype "passive"))
      (node (ref "C102") (pin "1") (pinfunction "1_1") (pintype "passive"))
      (node (ref "C103") (pin "1") (pinfunction "1_1") (pintype "passive"))
      (node (ref "C11") (pin "1") (pinfunction "1_1") (pintype "passive"))
      (node (ref "C12") (pin "2") (pinfunction "2_2") (pintype "passive"))
      (node (ref "C13") (pin "1") (pinfunction "1_1") (pintype "passive"))
      (node (ref "C14") (pin "1") (pinfunction "1_1") (pintype "passive"))
      (node (ref "C15") (pin "1") (pinfunction "1_1") (pintype "passive"))
      (node (ref "C16") (pin "1") (pinfunction "1_1") (pintype "passive"))
      (node (ref "C17") (pin "1") (pinfunction "1_1") (pintype "passive"))
      (node (ref "C19") (pin "2") (pinfunction "2_2") (pintype "passive"))
      (node (ref "C20") (pin "1") (pinfunction "1_1") (pintype "passive"))
      (node (ref "C21") (pin "1") (pinfunction "1_1") (pintype "passive"))
      (node (ref "C22") (pin "1") (pinfunction "1_1") (pintype "passive"))
      (node (ref "C23") (pin "1") (pinfunction "1_1") (pintype "passive"))
      (node (ref "C24") (pin "1") (pinfunction "1_1") (pintype "passive"))
      (node (ref "C25") (pin "1") (pinfunction "1_1") (pintype "passive"))
      (node (ref "C26") (pin "1") (pinfunction "1_1") (pintype "passive"))
      (node (ref "C29") (pin "1") (pinfunction "1_1") (pintype "passive"))
      (node (ref "C30") (pin "1") (pinfunction "1_1") (pintype "passive"))
      (node (ref "C32") (pin "1") (pinfunction "1_1") (pintype "passive"))
      (node (ref "C33") (pin "2") (pinfunction "2_2") (pintype "passive"))
      (node (ref "C34") (pin "1") (pinfunction "1_1") (pintype "passive"))
      (node (ref "C36") (pin "2") (pinfunction "2_2") (pintype "passive"))
      (node (ref "C37") (pin "1") (pinfunction "1_1") (pintype "passive"))
      (node (ref "C38") (pin "1") (pinfunction "1_1") (pintype "passive"))
      (node (ref "C39") (pin "1") (pinfunction "1_1") (pintype "passive"))
      (node (ref "C40") (pin "1") (pinfunction "1_1") (pintype "passive"))
      (node (ref "C41") (pin "1") (pinfunction "1_1") (pintype "passive"))
      (node (ref "C42") (pin "1") (pinfunction "1_1") (pintype "passive"))
      (node (ref "C43") (pin "1") (pinfunction "1_1") (pintype "passive"))
      (node (ref "C46") (pin "1") (pinfunction "1_1") (pintype "passive"))
      (node (ref "C47") (pin "1") (pinfunction "1_1") (pintype "passive"))
      (node (ref "C49") (pin "1") (pinfunction "1_1") (pintype "passive"))
      (node (ref "C50") (pin "2") (pinfunction "2_2") (pintype "passive"))
      (node (ref "C51") (pin "1") (pinfunction "1_1") (pintype "passive"))
      (node (ref "C53") (pin "2") (pinfunction "2_2") (pintype "passive"))
      (node (ref "C54") (pin "1") (pinfunction "1_1") (pintype "passive"))
      (node (ref "C55") (pin "1") (pinfunction "1_1") (pintype "passive"))
      (node (ref "C56") (pin "1") (pinfunction "1_1") (pintype "passive"))
      (node (ref "C57") (pin "1") (pinfunction "1_1") (pintype "passive"))
      (node (ref "C58") (pin "1") (pinfunction "1_1") (pintype "passive"))
      (node (ref "C59") (pin "1") (pinfunction "1_1") (pintype "passive"))
      (node (ref "C60") (pin "1") (pinfunction "1_1") (pintype "passive"))
      (node (ref "C63") (pin "1") (pinfunction "1_1") (pintype "passive"))
      (node (ref "C64") (pin "1") (pinfunction "1_1") (pintype "passive"))
      (node (ref "C66") (pin "1") (pinfunction "1_1") (pintype "passive"))
      (node (ref "C67") (pin "2") (pinfunction "2_2") (pintype "passive"))
      (node (ref "C68") (pin "1") (pinfunction "1_1") (pintype "passive"))
      (node (ref "C70") (pin "2") (pinfunction "2_2") (pintype "passive"))
      (node (ref "C71") (pin "1") (pinfunction "1_1") (pintype "passive"))
      (node (ref "C72") (pin "1") (pinfunction "1_1") (pintype "passive"))
      (node (ref "C73") (pin "1") (pinfunction "1_1") (pintype "passive"))
      (node (ref "C74") (pin "1") (pinfunction "1_1") (pintype "passive"))
      (node (ref "C75") (pin "1") (pinfunction "1_1") (pintype "passive"))
      (node (ref "C76") (pin "1") (pinfunction "1_1") (pintype "passive"))
      (node (ref "C77") (pin "1") (pinfunction "1_1") (pintype "passive"))
      (node (ref "C80") (pin "1") (pinfunction "1_1") (pintype "passive"))
      (node (ref "C81") (pin "1") (pinfunction "1_1") (pintype "passive"))
      (node (ref "C83") (pin "1") (pinfunction "1_1") (pintype "passive"))
      (node (ref "C84") (pin "2") (pinfunction "2_2") (pintype "passive"))
      (node (ref "C85") (pin "1") (pinfunction "1_1") (pintype "passive"))
      (node (ref "C87") (pin "2") (pinfunction "2_2") (pintype "passive"))
      (node (ref "C88") (pin "1") (pinfunction "1_1") (pintype "passive"))
      (node (ref "C89") (pin "1") (pinfunction "1_1") (pintype "passive"))
      (node (ref "C90") (pin "1") (pinfunction "1_1") (pintype "passive"))
      (node (ref "C91") (pin "1") (pinfunction "1_1") (pintype "passive"))
      (node (ref "C92") (pin "1") (pinfunction "1_1") (pintype "passive"))
      (node (ref "C93") (pin "1") (pinfunction "1_1") (pintype "passive"))
      (node (ref "C94") (pin "1") (pinfunction "1_1") (pintype "passive"))
      (node (ref "C97") (pin "1") (pinfunction "1_1") (pintype "passive"))
      (node (ref "C98") (pin "1") (pinfunction "1_1") (pintype "passive"))
      (node (ref "D2") (pin "1") (pinfunction "A_1") (pintype "passive"))
      (node (ref "D3") (pin "1") (pinfunction "1_1") (pintype "passive"))
      (node (ref "D4") (pin "1") (pinfunction "A_1") (pintype "passive"))
      (node (ref "D5") (pin "1") (pinfunction "A_1") (pintype "passive"))
      (node (ref "D6") (pin "1") (pinfunction "A_1") (pintype "passive"))
      (node (ref "D7") (pin "1") (pinfunction "A_1") (pintype "passive"))
      (node (ref "D8") (pin "1") (pinfunction "A_1") (pintype "passive"))
      (node (ref "DF1") (pin "1") (pinfunction "A_1") (pintype "passive"))
      (node (ref "DF1") (pin "3") (pinfunction "C_3") (pintype "passive"))
      (node (ref "JP2") (pin "1") (pinfunction "1_1") (pintype "passive"))
      (node (ref "JP5") (pin "5") (pinfunction "5_5") (pintype "passive"))
      (node (ref "JP5") (pin "6") (pinfunction "6_6") (pintype "passive"))
      (node (ref "LED2") (pin "2") (pinfunction "K_2") (pintype "passive"))
      (node (ref "LED3") (pin "2") (pinfunction "K_2") (pintype "passive"))
      (node (ref "LED4") (pin "2") (pinfunction "K_2") (pintype "passive"))
      (node (ref "LED5") (pin "2") (pinfunction "K_2") (pintype "passive"))
      (node (ref "LED6") (pin "2") (pinfunction "K_2") (pintype "passive"))
      (node (ref "LED7") (pin "2") (pinfunction "K_2") (pintype "passive"))
      (node (ref "R17") (pin "2") (pinfunction "2_2") (pintype "passive"))
      (node (ref "R19") (pin "2") (pinfunction "2_2") (pintype "passive"))
      (node (ref "R21") (pin "1") (pinfunction "1_1") (pintype "passive"))
      (node (ref "R30") (pin "2") (pinfunction "2_2") (pintype "passive"))
      (node (ref "R32") (pin "2") (pinfunction "2_2") (pintype "passive"))
      (node (ref "R34") (pin "1") (pinfunction "1_1") (pintype "passive"))
      (node (ref "R43") (pin "2") (pinfunction "2_2") (pintype "passive"))
      (node (ref "R45") (pin "2") (pinfunction "2_2") (pintype "passive"))
      (node (ref "R47") (pin "1") (pinfunction "1_1") (pintype "passive"))
      (node (ref "R56") (pin "2") (pinfunction "2_2") (pintype "passive"))
      (node (ref "R58") (pin "2") (pinfunction "2_2") (pintype "passive"))
      (node (ref "R60") (pin "1") (pinfunction "1_1") (pintype "passive"))
      (node (ref "R69") (pin "2") (pinfunction "2_2") (pintype "passive"))
      (node (ref "R7") (pin "2") (pinfunction "2_2") (pintype "passive"))
      (node (ref "R71") (pin "2") (pinfunction "2_2") (pintype "passive"))
      (node (ref "R73") (pin "1") (pinfunction "1_1") (pintype "passive"))
      (node (ref "R75") (pin "1") (pinfunction "1_1") (pintype "passive"))
      (node (ref "R8") (pin "1") (pinfunction "1_1") (pintype "passive"))
      (node (ref "U10") (pin "1") (pinfunction "SYNC_1") (pintype "passive"))
      (node (ref "U10") (pin "10") (pinfunction "PGND_10") (pintype "passive"))
      (node (ref "U10") (pin "11") (pinfunction "GND_11") (pintype "passive"))
      (node (ref "U10") (pin "12") (pinfunction "GND_12") (pintype "passive"))
      (node (ref "U10") (pin "13") (pinfunction "GND_13") (pintype "passive"))
      (node (ref "U10") (pin "14") (pinfunction "GND_14") (pintype "passive"))
      (node (ref "U10") (pin "25") (pinfunction "NC_25") (pintype "passive"))
      (node (ref "U10") (pin "26") (pinfunction "NC_26") (pintype "passive"))
      (node (ref "U10") (pin "27") (pinfunction "NC_27") (pintype "passive"))
      (node (ref "U10") (pin "28") (pinfunction "NC_28") (pintype "passive"))
      (node (ref "U10") (pin "29") (pinfunction "GND_29") (pintype "passive"))
      (node (ref "U10") (pin "8") (pinfunction "PGND_8") (pintype "passive"))
      (node (ref "U10") (pin "9") (pinfunction "PGND_9") (pintype "passive"))
      (node (ref "U12") (pin "17") (pinfunction "GND_17") (pintype "passive"))
      (node (ref "U12") (pin "4") (pinfunction "VCCUV_4") (pintype "passive"))
      (node (ref "U12") (pin "6") (pinfunction "TIMER_6") (pintype "passive"))
      (node (ref "U12") (pin "8") (pinfunction "OVLO_8") (pintype "passive"))
      (node (ref "U13") (pin "1") (pinfunction "SYNC_1") (pintype "passive"))
      (node (ref "U13") (pin "10") (pinfunction "PGND_10") (pintype "passive"))
      (node (ref "U13") (pin "11") (pinfunction "GND_11") (pintype "passive"))
      (node (ref "U13") (pin "12") (pinfunction "GND_12") (pintype "passive"))
      (node (ref "U13") (pin "13") (pinfunction "GND_13") (pintype "passive"))
      (node (ref "U13") (pin "14") (pinfunction "GND_14") (pintype "passive"))
      (node (ref "U13") (pin "25") (pinfunction "NC_25") (pintype "passive"))
      (node (ref "U13") (pin "26") (pinfunction "NC_26") (pintype "passive"))
      (node (ref "U13") (pin "27") (pinfunction "NC_27") (pintype "passive"))
      (node (ref "U13") (pin "28") (pinfunction "NC_28") (pintype "passive"))
      (node (ref "U13") (pin "29") (pinfunction "GND_29") (pintype "passive"))
      (node (ref "U13") (pin "8") (pinfunction "PGND_8") (pintype "passive"))
      (node (ref "U13") (pin "9") (pinfunction "PGND_9") (pintype "passive"))
      (node (ref "U15") (pin "17") (pinfunction "GND_17") (pintype "passive"))
      (node (ref "U15") (pin "4") (pinfunction "VCCUV_4") (pintype "passive"))
      (node (ref "U15") (pin "6") (pinfunction "TIMER_6") (pintype "passive"))
      (node (ref "U15") (pin "8") (pinfunction "OVLO_8") (pintype "passive"))
      (node (ref "U16") (pin "1") (pinfunction "SYNC_1") (pintype "passive"))
      (node (ref "U16") (pin "10") (pinfunction "PGND_10") (pintype "passive"))
      (node (ref "U16") (pin "11") (pinfunction "GND_11") (pintype "passive"))
      (node (ref "U16") (pin "12") (pinfunction "GND_12") (pintype "passive"))
      (node (ref "U16") (pin "13") (pinfunction "GND_13") (pintype "passive"))
      (node (ref "U16") (pin "14") (pinfunction "GND_14") (pintype "passive"))
      (node (ref "U16") (pin "25") (pinfunction "NC_25") (pintype "passive"))
      (node (ref "U16") (pin "26") (pinfunction "NC_26") (pintype "passive"))
      (node (ref "U16") (pin "27") (pinfunction "NC_27") (pintype "passive"))
      (node (ref "U16") (pin "28") (pinfunction "NC_28") (pintype "passive"))
      (node (ref "U16") (pin "29") (pinfunction "GND_29") (pintype "passive"))
      (node (ref "U16") (pin "8") (pinfunction "PGND_8") (pintype "passive"))
      (node (ref "U16") (pin "9") (pinfunction "PGND_9") (pintype "passive"))
      (node (ref "U18") (pin "17") (pinfunction "GND_17") (pintype "passive"))
      (node (ref "U18") (pin "4") (pinfunction "VCCUV_4") (pintype "passive"))
      (node (ref "U18") (pin "6") (pinfunction "TIMER_6") (pintype "passive"))
      (node (ref "U18") (pin "8") (pinfunction "OVLO_8") (pintype "passive"))
      (node (ref "U2") (pin "6") (pinfunction "GND_6") (pintype "passive"))
      (node (ref "U2") (pin "9") (pinfunction "PAD_9") (pintype "passive"))
      (node (ref "U3") (pin "1") (pinfunction "GND_1") (pintype "passive"))
      (node (ref "U4") (pin "1") (pinfunction "SYNC_1") (pintype "passive"))
      (node (ref "U4") (pin "10") (pinfunction "PGND_10") (pintype "passive"))
      (node (ref "U4") (pin "11") (pinfunction "GND_11") (pintype "passive"))
      (node (ref "U4") (pin "12") (pinfunction "GND_12") (pintype "passive"))
      (node (ref "U4") (pin "13") (pinfunction "GND_13") (pintype "passive"))
      (node (ref "U4") (pin "14") (pinfunction "GND_14") (pintype "passive"))
      (node (ref "U4") (pin "25") (pinfunction "NC_25") (pintype "passive"))
      (node (ref "U4") (pin "26") (pinfunction "NC_26") (pintype "passive"))
      (node (ref "U4") (pin "27") (pinfunction "NC_27") (pintype "passive"))
      (node (ref "U4") (pin "28") (pinfunction "NC_28") (pintype "passive"))
      (node (ref "U4") (pin "29") (pinfunction "GND_29") (pintype "passive"))
      (node (ref "U4") (pin "8") (pinfunction "PGND_8") (pintype "passive"))
      (node (ref "U4") (pin "9") (pinfunction "PGND_9") (pintype "passive"))
      (node (ref "U6") (pin "17") (pinfunction "GND_17") (pintype "passive"))
      (node (ref "U6") (pin "4") (pinfunction "VCCUV_4") (pintype "passive"))
      (node (ref "U6") (pin "6") (pinfunction "TIMER_6") (pintype "passive"))
      (node (ref "U6") (pin "8") (pinfunction "OVLO_8") (pintype "passive"))
      (node (ref "U7") (pin "1") (pinfunction "SYNC_1") (pintype "passive"))
      (node (ref "U7") (pin "10") (pinfunction "PGND_10") (pintype "passive"))
      (node (ref "U7") (pin "11") (pinfunction "GND_11") (pintype "passive"))
      (node (ref "U7") (pin "12") (pinfunction "GND_12") (pintype "passive"))
      (node (ref "U7") (pin "13") (pinfunction "GND_13") (pintype "passive"))
      (node (ref "U7") (pin "14") (pinfunction "GND_14") (pintype "passive"))
      (node (ref "U7") (pin "25") (pinfunction "NC_25") (pintype "passive"))
      (node (ref "U7") (pin "26") (pinfunction "NC_26") (pintype "passive"))
      (node (ref "U7") (pin "27") (pinfunction "NC_27") (pintype "passive"))
      (node (ref "U7") (pin "28") (pinfunction "NC_28") (pintype "passive"))
      (node (ref "U7") (pin "29") (pinfunction "GND_29") (pintype "passive"))
      (node (ref "U7") (pin "8") (pinfunction "PGND_8") (pintype "passive"))
      (node (ref "U7") (pin "9") (pinfunction "PGND_9") (pintype "passive"))
      (node (ref "U9") (pin "17") (pinfunction "GND_17") (pintype "passive"))
      (node (ref "U9") (pin "4") (pinfunction "VCCUV_4") (pintype "passive"))
      (node (ref "U9") (pin "6") (pinfunction "TIMER_6") (pintype "passive"))
      (node (ref "U9") (pin "8") (pinfunction "OVLO_8") (pintype "passive"))
    )
    (net (code "29") (name "Net-(C13-Pad2)") (class "Default")
      (node (ref "C13") (pin "2") (pinfunction "2_2") (pintype "passive"))
      (node (ref "JP14") (pin "1") (pinfunction "1_1") (pintype "passive"))
      (node (ref "JP15") (pin "1") (pinfunction "1_1") (pintype "passive"))
      (node (ref "JP16") (pin "1") (pinfunction "1_1") (pintype "passive"))
      (node (ref "JP17") (pin "1") (pinfunction "1_1") (pintype "passive"))
      (node (ref "R75") (pin "2") (pinfunction "2_2") (pintype "passive"))
    )
    (net (code "30") (name "Net-(C18-Pad1)") (class "Default")
      (node (ref "C18") (pin "1") (pinfunction "1_1") (pintype "passive"))
      (node (ref "L2") (pin "1") (pinfunction "1_1") (pintype "passive"))
      (node (ref "U4") (pin "15") (pinfunction "SW_15") (pintype "passive"))
      (node (ref "U4") (pin "16") (pinfunction "SW_16") (pintype "passive"))
      (node (ref "U4") (pin "17") (pinfunction "SW_17") (pintype "passive"))
      (node (ref "U4") (pin "18") (pinfunction "SW_18") (pintype "passive"))
      (node (ref "U4") (pin "19") (pinfunction "SW_19") (pintype "passive"))
    )
    (net (code "31") (name "Net-(C35-Pad1)") (class "Default")
      (node (ref "C35") (pin "1") (pinfunction "1_1") (pintype "passive"))
      (node (ref "L3") (pin "1") (pinfunction "1_1") (pintype "passive"))
      (node (ref "U7") (pin "15") (pinfunction "SW_15") (pintype "passive"))
      (node (ref "U7") (pin "16") (pinfunction "SW_16") (pintype "passive"))
      (node (ref "U7") (pin "17") (pinfunction "SW_17") (pintype "passive"))
      (node (ref "U7") (pin "18") (pinfunction "SW_18") (pintype "passive"))
      (node (ref "U7") (pin "19") (pinfunction "SW_19") (pintype "passive"))
    )
    (net (code "32") (name "Net-(C52-Pad1)") (class "Default")
      (node (ref "C52") (pin "1") (pinfunction "1_1") (pintype "passive"))
      (node (ref "L4") (pin "1") (pinfunction "1_1") (pintype "passive"))
      (node (ref "U10") (pin "15") (pinfunction "SW_15") (pintype "passive"))
      (node (ref "U10") (pin "16") (pinfunction "SW_16") (pintype "passive"))
      (node (ref "U10") (pin "17") (pinfunction "SW_17") (pintype "passive"))
      (node (ref "U10") (pin "18") (pinfunction "SW_18") (pintype "passive"))
      (node (ref "U10") (pin "19") (pinfunction "SW_19") (pintype "passive"))
    )
    (net (code "33") (name "Net-(C69-Pad1)") (class "Default")
      (node (ref "C69") (pin "1") (pinfunction "1_1") (pintype "passive"))
      (node (ref "L5") (pin "1") (pinfunction "1_1") (pintype "passive"))
      (node (ref "U13") (pin "15") (pinfunction "SW_15") (pintype "passive"))
      (node (ref "U13") (pin "16") (pinfunction "SW_16") (pintype "passive"))
      (node (ref "U13") (pin "17") (pinfunction "SW_17") (pintype "passive"))
      (node (ref "U13") (pin "18") (pinfunction "SW_18") (pintype "passive"))
      (node (ref "U13") (pin "19") (pinfunction "SW_19") (pintype "passive"))
    )
    (net (code "34") (name "Net-(C86-Pad1)") (class "Default")
      (node (ref "C86") (pin "1") (pinfunction "1_1") (pintype "passive"))
      (node (ref "L6") (pin "1") (pinfunction "1_1") (pintype "passive"))
      (node (ref "U16") (pin "15") (pinfunction "SW_15") (pintype "passive"))
      (node (ref "U16") (pin "16") (pinfunction "SW_16") (pintype "passive"))
      (node (ref "U16") (pin "17") (pinfunction "SW_17") (pintype "passive"))
      (node (ref "U16") (pin "18") (pinfunction "SW_18") (pintype "passive"))
      (node (ref "U16") (pin "19") (pinfunction "SW_19") (pintype "passive"))
    )
    (net (code "35") (name "Net-(D2-K)") (class "Default")
      (node (ref "C103") (pin "2") (pinfunction "2_2") (pintype "passive"))
      (node (ref "C12") (pin "1") (pinfunction "1_1") (pintype "passive"))
      (node (ref "C19") (pin "1") (pinfunction "1_1") (pintype "passive"))
      (node (ref "C20") (pin "2") (pinfunction "2_2") (pintype "passive"))
      (node (ref "C21") (pin "2") (pinfunction "2_2") (pintype "passive"))
      (node (ref "C36") (pin "1") (pinfunction "1_1") (pintype "passive"))
      (node (ref "C37") (pin "2") (pinfunction "2_2") (pintype "passive"))
      (node (ref "C38") (pin "2") (pinfunction "2_2") (pintype "passive"))
      (node (ref "C53") (pin "1") (pinfunction "1_1") (pintype "passive"))
      (node (ref "C54") (pin "2") (pinfunction "2_2") (pintype "passive"))
      (node (ref "C55") (pin "2") (pinfunction "2_2") (pintype "passive"))
      (node (ref "C70") (pin "1") (pinfunction "1_1") (pintype "passive"))
      (node (ref "C71") (pin "2") (pinfunction "2_2") (pintype "passive"))
      (node (ref "C72") (pin "2") (pinfunction "2_2") (pintype "passive"))
      (node (ref "C87") (pin "1") (pinfunction "1_1") (pintype "passive"))
      (node (ref "C88") (pin "2") (pinfunction "2_2") (pintype "passive"))
      (node (ref "C89") (pin "2") (pinfunction "2_2") (pintype "passive"))
      (node (ref "D2") (pin "2") (pinfunction "K_2") (pintype "passive"))
      (node (ref "DF1") (pin "2") (pinfunction "B_2") (pintype "passive"))
      (node (ref "FU1") (pin "2") (pinfunction "2_2") (pintype "passive"))
      (node (ref "R5") (pin "2") (pinfunction "2_2") (pintype "passive"))
      (node (ref "R6") (pin "1") (pinfunction "1_1") (pintype "passive"))
      (node (ref "U10") (pin "5") (pinfunction "VIN_5") (pintype "passive"))
      (node (ref "U10") (pin "6") (pinfunction "VIN_6") (pintype "passive"))
      (node (ref "U10") (pin "7") (pinfunction "VIN_7") (pintype "passive"))
      (node (ref "U13") (pin "5") (pinfunction "VIN_5") (pintype "passive"))
      (node (ref "U13") (pin "6") (pinfunction "VIN_6") (pintype "passive"))
      (node (ref "U13") (pin "7") (pinfunction "VIN_7") (pintype "passive"))
      (node (ref "U16") (pin "5") (pinfunction "VIN_5") (pintype "passive"))
      (node (ref "U16") (pin "6") (pinfunction "VIN_6") (pintype "passive"))
      (node (ref "U16") (pin "7") (pinfunction "VIN_7") (pintype "passive"))
      (node (ref "U2") (pin "7") (pinfunction "VIN_7") (pintype "passive"))
      (node (ref "U4") (pin "5") (pinfunction "VIN_5") (pintype "passive"))
      (node (ref "U4") (pin "6") (pinfunction "VIN_6") (pintype "passive"))
      (node (ref "U4") (pin "7") (pinfunction "VIN_7") (pintype "passive"))
      (node (ref "U7") (pin "5") (pinfunction "VIN_5") (pintype "passive"))
      (node (ref "U7") (pin "6") (pinfunction "VIN_6") (pintype "passive"))
      (node (ref "U7") (pin "7") (pinfunction "VIN_7") (pintype "passive"))
    )
    (net (code "36") (name "Net-(FU1-Pad1)") (class "Default")
      (node (ref "FU1") (pin "1") (pinfunction "1_1") (pintype "passive"))
      (node (ref "JP2") (pin "2") (pinfunction "2_2") (pintype "passive"))
    )
    (net (code "37") (name "Net-(LED2-A)") (class "Default")
      (node (ref "LED2") (pin "1") (pinfunction "A_1") (pintype "passive"))
      (node (ref "R5") (pin "1") (pinfunction "1_1") (pintype "passive"))
    )
    (net (code "38") (name "Net-(LED3-A)") (class "Default")
      (node (ref "LED3") (pin "1") (pinfunction "A_1") (pintype "passive"))
      (node (ref "R11") (pin "1") (pinfunction "1_1") (pintype "passive"))
    )
    (net (code "39") (name "Net-(LED4-A)") (class "Default")
      (node (ref "LED4") (pin "1") (pinfunction "A_1") (pintype "passive"))
      (node (ref "R24") (pin "1") (pinfunction "1_1") (pintype "passive"))
    )
    (net (code "40") (name "Net-(LED5-A)") (class "Default")
      (node (ref "LED5") (pin "1") (pinfunction "A_1") (pintype "passive"))
      (node (ref "R37") (pin "1") (pinfunction "1_1") (pintype "passive"))
    )
    (net (code "41") (name "Net-(LED6-A)") (class "Default")
      (node (ref "LED6") (pin "1") (pinfunction "A_1") (pintype "passive"))
      (node (ref "R50") (pin "1") (pinfunction "1_1") (pintype "passive"))
    )
    (net (code "42") (name "Net-(LED7-A)") (class "Default")
      (node (ref "LED7") (pin "1") (pinfunction "A_1") (pintype "passive"))
      (node (ref "R63") (pin "1") (pinfunction "1_1") (pintype "passive"))
    )
    (net (code "43") (name "Net-(R13-Pad1)") (class "Default")
      (node (ref "R13") (pin "1") (pinfunction "1_1") (pintype "passive"))
      (node (ref "R9") (pin "1") (pinfunction "1_1") (pintype "passive"))
      (node (ref "U5") (pin "5") (pinfunction "D_5") (pintype "passive"))
      (node (ref "U5") (pin "6") (pinfunction "D_6") (pintype "passive"))
      (node (ref "U5") (pin "7") (pinfunction "D_7") (pintype "passive"))
      (node (ref "U5") (pin "8") (pinfunction "D_8") (pintype "passive"))
    )
    (net (code "44") (name "Net-(R22-Pad1)") (class "Default")
      (node (ref "R22") (pin "1") (pinfunction "1_1") (pintype "passive"))
      (node (ref "R26") (pin "1") (pinfunction "1_1") (pintype "passive"))
      (node (ref "U8") (pin "5") (pinfunction "D_5") (pintype "passive"))
      (node (ref "U8") (pin "6") (pinfunction "D_6") (pintype "passive"))
      (node (ref "U8") (pin "7") (pinfunction "D_7") (pintype "passive"))
      (node (ref "U8") (pin "8") (pinfunction "D_8") (pintype "passive"))
    )
    (net (code "45") (name "Net-(R35-Pad1)") (class "Default")
      (node (ref "R35") (pin "1") (pinfunction "1_1") (pintype "passive"))
      (node (ref "R39") (pin "1") (pinfunction "1_1") (pintype "passive"))
      (node (ref "U11") (pin "5") (pinfunction "D_5") (pintype "passive"))
      (node (ref "U11") (pin "6") (pinfunction "D_6") (pintype "passive"))
      (node (ref "U11") (pin "7") (pinfunction "D_7") (pintype "passive"))
      (node (ref "U11") (pin "8") (pinfunction "D_8") (pintype "passive"))
    )
    (net (code "46") (name "Net-(R48-Pad1)") (class "Default")
      (node (ref "R48") (pin "1") (pinfunction "1_1") (pintype "passive"))
      (node (ref "R52") (pin "1") (pinfunction "1_1") (pintype "passive"))
      (node (ref "U14") (pin "5") (pinfunction "D_5") (pintype "passive"))
      (node (ref "U14") (pin "6") (pinfunction "D_6") (pintype "passive"))
      (node (ref "U14") (pin "7") (pinfunction "D_7") (pintype "passive"))
      (node (ref "U14") (pin "8") (pinfunction "D_8") (pintype "passive"))
    )
    (net (code "47") (name "Net-(R61-Pad1)") (class "Default")
      (node (ref "R61") (pin "1") (pinfunction "1_1") (pintype "passive"))
      (node (ref "R65") (pin "1") (pinfunction "1_1") (pintype "passive"))
      (node (ref "U17") (pin "5") (pinfunction "D_5") (pintype "passive"))
      (node (ref "U17") (pin "6") (pinfunction "D_6") (pintype "passive"))
      (node (ref "U17") (pin "7") (pinfunction "D_7") (pintype "passive"))
      (node (ref "U17") (pin "8") (pinfunction "D_8") (pintype "passive"))
    )
    (net (code "48") (name "Net-(U2-BOOT)") (class "Default")
      (node (ref "C9") (pin "1") (pinfunction "1_1") (pintype "passive"))
      (node (ref "U2") (pin "1") (pinfunction "BOOT_1") (pintype "passive"))
    )
    (net (code "49") (name "Net-(U2-EN)") (class "Default")
      (node (ref "R6") (pin "2") (pinfunction "2_2") (pintype "passive"))
      (node (ref "R7") (pin "1") (pinfunction "1_1") (pintype "passive"))
      (node (ref "U2") (pin "5") (pinfunction "EN_5") (pintype "passive"))
    )
    (net (code "50") (name "Net-(U2-PH)") (class "Default")
      (node (ref "C9") (pin "2") (pinfunction "2_2") (pintype "passive"))
      (node (ref "D3") (pin "2") (pinfunction "2_2") (pintype "passive"))
      (node (ref "L1") (pin "1") (pinfunction "1_1") (pintype "passive"))
      (node (ref "U2") (pin "8") (pinfunction "PH_8") (pintype "passive"))
    )
    (net (code "51") (name "Net-(U2-VSENSE)") (class "Default")
      (node (ref "R4") (pin "1") (pinfunction "1_1") (pintype "passive"))
      (node (ref "R8") (pin "2") (pinfunction "2_2") (pintype "passive"))
      (node (ref "U2") (pin "4") (pinfunction "VSENSE_4") (pintype "passive"))
    )
    (net (code "52") (name "Net-(U4-BIAS)") (class "Default")
      (node (ref "R15") (pin "2") (pinfunction "2_2") (pintype "passive"))
      (node (ref "U4") (pin "22") (pinfunction "BIAS_22") (pintype "passive"))
    )
    (net (code "53") (name "Net-(U4-BST)") (class "Default")
      (node (ref "C18") (pin "2") (pinfunction "2_2") (pintype "passive"))
      (node (ref "U4") (pin "20") (pinfunction "BST_20") (pintype "passive"))
    )
    (net (code "54") (name "Net-(U4-EN{slash}UV)") (class "Default")
      (node (ref "R10") (pin "1") (pinfunction "1_1") (pintype "passive"))
      (node (ref "U4") (pin "4") (pinfunction "EN/UV_4") (pintype "passive"))
    )
    (net (code "55") (name "Net-(U4-FB)") (class "Default")
      (node (ref "C31") (pin "2") (pinfunction "2_2") (pintype "passive"))
      (node (ref "R18") (pin "2") (pinfunction "2_2") (pintype "passive"))
      (node (ref "R19") (pin "1") (pinfunction "1_1") (pintype "passive"))
      (node (ref "U4") (pin "24") (pinfunction "FB_24") (pintype "passive"))
    )
    (net (code "56") (name "Net-(U4-INTVCC)") (class "Default")
      (node (ref "C29") (pin "2") (pinfunction "2_2") (pintype "passive"))
      (node (ref "U4") (pin "21") (pinfunction "INTVCC_21") (pintype "passive"))
    )
    (net (code "57") (name "Net-(U4-PG)") (class "Default")
      (node (ref "R16") (pin "2") (pinfunction "2_2") (pintype "passive"))
      (node (ref "U4") (pin "23") (pinfunction "PG_23") (pintype "passive"))
    )
    (net (code "58") (name "Net-(U4-RT)") (class "Default")
      (node (ref "R17") (pin "1") (pinfunction "1_1") (pintype "passive"))
      (node (ref "U4") (pin "3") (pinfunction "RT_3") (pintype "passive"))
    )
    (net (code "59") (name "Net-(U4-TR{slash}SS)") (class "Default")
      (node (ref "C30") (pin "2") (pinfunction "2_2") (pintype "passive"))
      (node (ref "U4") (pin "2") (pinfunction "TR/SS_2") (pintype "passive"))
    )
    (net (code "60") (name "Net-(U5-G)") (class "Default")
      (node (ref "R14") (pin "1") (pinfunction "1_1") (pintype "passive"))
      (node (ref "U5") (pin "4") (pinfunction "G_4") (pintype "passive"))
    )
    (net (code "61") (name "Net-(U6-BST)") (class "Default")
      (node (ref "C28") (pin "2") (pinfunction "2_2") (pintype "passive"))
      (node (ref "U6") (pin "14") (pinfunction "BST_14") (pintype "passive"))
    )
    (net (code "62") (name "Net-(U6-ISET)") (class "Default")
      (node (ref "R21") (pin "2") (pinfunction "2_2") (pintype "passive"))
      (node (ref "U6") (pin "9") (pinfunction "ISET_9") (pintype "passive"))
    )
    (net (code "63") (name "Net-(U6-RUN)") (class "Default")
      (node (ref "C22") (pin "2") (pinfunction "2_2") (pintype "passive"))
      (node (ref "C23") (pin "2") (pinfunction "2_2") (pintype "passive"))
      (node (ref "C24") (pin "2") (pinfunction "2_2") (pintype "passive"))
      (node (ref "C27") (pin "2") (pinfunction "2_2") (pintype "passive"))
      (node (ref "C31") (pin "1") (pinfunction "1_1") (pintype "passive"))
      (node (ref "C32") (pin "2") (pinfunction "2_2") (pintype "passive"))
      (node (ref "L2") (pin "2") (pinfunction "2_2") (pintype "passive"))
      (node (ref "R11") (pin "2") (pinfunction "2_2") (pintype "passive"))
      (node (ref "R15") (pin "1") (pinfunction "1_1") (pintype "passive"))
      (node (ref "R16") (pin "1") (pinfunction "1_1") (pintype "passive"))
      (node (ref "R18") (pin "1") (pinfunction "1_1") (pintype "passive"))
      (node (ref "R9") (pin "2") (pinfunction "2_2") (pintype "passive"))
      (node (ref "U6") (pin "1") (pinfunction "RUN_1") (pintype "passive"))
      (node (ref "U6") (pin "16") (pinfunction "SNS+_16") (pintype "passive"))
      (node (ref "U6") (pin "2") (pinfunction "VIN_2") (pintype "passive"))
    )
    (net (code "64") (name "Net-(U6-SNS-)") (class "Default")
      (node (ref "C27") (pin "1") (pinfunction "1_1") (pintype "passive"))
      (node (ref "R13") (pin "2") (pinfunction "2_2") (pintype "passive"))
      (node (ref "U6") (pin "15") (pinfunction "SNS-_15") (pintype "passive"))
    )
    (net (code "65") (name "Net-(U6-TGDN)") (class "Default")
      (node (ref "R14") (pin "2") (pinfunction "2_2") (pintype "passive"))
      (node (ref "U6") (pin "11") (pinfunction "TGDN_11") (pintype "passive"))
      (node (ref "U6") (pin "12") (pinfunction "TGUP_12") (pintype "passive"))
    )
    (net (code "66") (name "Net-(U6-VCC)") (class "Default")
      (node (ref "C34") (pin "2") (pinfunction "2_2") (pintype "passive"))
      (node (ref "R20") (pin "1") (pinfunction "1_1") (pintype "passive"))
      (node (ref "U6") (pin "3") (pinfunction "VCC_3") (pintype "passive"))
    )
    (net (code "67") (name "Net-(U6-~{FAULT})") (class "Default")
      (node (ref "R20") (pin "2") (pinfunction "2_2") (pintype "passive"))
      (node (ref "U6") (pin "5") (pinfunction "~{FAULT}_5") (pintype "passive"))
    )
    (net (code "68") (name "Net-(U7-BIAS)") (class "Default")
      (node (ref "R28") (pin "2") (pinfunction "2_2") (pintype "passive"))
      (node (ref "U7") (pin "22") (pinfunction "BIAS_22") (pintype "passive"))
    )
    (net (code "69") (name "Net-(U7-BST)") (class "Default")
      (node (ref "C35") (pin "2") (pinfunction "2_2") (pintype "passive"))
      (node (ref "U7") (pin "20") (pinfunction "BST_20") (pintype "passive"))
    )
    (net (code "70") (name "Net-(U7-EN{slash}UV)") (class "Default")
      (node (ref "R23") (pin "1") (pinfunction "1_1") (pintype "passive"))
      (node (ref "U7") (pin "4") (pinfunction "EN/UV_4") (pintype "passive"))
    )
    (net (code "71") (name "Net-(U7-FB)") (class "Default")
      (node (ref "C48") (pin "2") (pinfunction "2_2") (pintype "passive"))
      (node (ref "R31") (pin "2") (pinfunction "2_2") (pintype "passive"))
      (node (ref "R32") (pin "1") (pinfunction "1_1") (pintype "passive"))
      (node (ref "U7") (pin "24") (pinfunction "FB_24") (pintype "passive"))
    )
    (net (code "72") (name "Net-(U7-INTVCC)") (class "Default")
      (node (ref "C46") (pin "2") (pinfunction "2_2") (pintype "passive"))
      (node (ref "U7") (pin "21") (pinfunction "INTVCC_21") (pintype "passive"))
    )
    (net (code "73") (name "Net-(U7-PG)") (class "Default")
      (node (ref "R29") (pin "2") (pinfunction "2_2") (pintype "passive"))
      (node (ref "U7") (pin "23") (pinfunction "PG_23") (pintype "passive"))
    )
    (net (code "74") (name "Net-(U7-RT)") (class "Default")
      (node (ref "R30") (pin "1") (pinfunction "1_1") (pintype "passive"))
      (node (ref "U7") (pin "3") (pinfunction "RT_3") (pintype "passive"))
    )
    (net (code "75") (name "Net-(U7-TR{slash}SS)") (class "Default")
      (node (ref "C47") (pin "2") (pinfunction "2_2") (pintype "passive"))
      (node (ref "U7") (pin "2") (pinfunction "TR/SS_2") (pintype "passive"))
    )
    (net (code "76") (name "Net-(U8-G)") (class "Default")
      (node (ref "R27") (pin "1") (pinfunction "1_1") (pintype "passive"))
      (node (ref "U8") (pin "4") (pinfunction "G_4") (pintype "passive"))
    )
    (net (code "77") (name "Net-(U9-BST)") (class "Default")
      (node (ref "C45") (pin "2") (pinfunction "2_2") (pintype "passive"))
      (node (ref "U9") (pin "14") (pinfunction "BST_14") (pintype "passive"))
    )
    (net (code "78") (name "Net-(U9-ISET)") (class "Default")
      (node (ref "R34") (pin "2") (pinfunction "2_2") (pintype "passive"))
      (node (ref "U9") (pin "9") (pinfunction "ISET_9") (pintype "passive"))
    )
    (net (code "79") (name "Net-(U9-RUN)") (class "Default")
      (node (ref "C39") (pin "2") (pinfunction "2_2") (pintype "passive"))
      (node (ref "C40") (pin "2") (pinfunction "2_2") (pintype "passive"))
      (node (ref "C41") (pin "2") (pinfunction "2_2") (pintype "passive"))
      (node (ref "C44") (pin "2") (pinfunction "2_2") (pintype "passive"))
      (node (ref "C48") (pin "1") (pinfunction "1_1") (pintype "passive"))
      (node (ref "C49") (pin "2") (pinfunction "2_2") (pintype "passive"))
      (node (ref "L3") (pin "2") (pinfunction "2_2") (pintype "passive"))
      (node (ref "R22") (pin "2") (pinfunction "2_2") (pintype "passive"))
      (node (ref "R24") (pin "2") (pinfunction "2_2") (pintype "passive"))
      (node (ref "R28") (pin "1") (pinfunction "1_1") (pintype "passive"))
      (node (ref "R29") (pin "1") (pinfunction "1_1") (pintype "passive"))
      (node (ref "R31") (pin "1") (pinfunction "1_1") (pintype "passive"))
      (node (ref "U9") (pin "1") (pinfunction "RUN_1") (pintype "passive"))
      (node (ref "U9") (pin "16") (pinfunction "SNS+_16") (pintype "passive"))
      (node (ref "U9") (pin "2") (pinfunction "VIN_2") (pintype "passive"))
    )
    (net (code "80") (name "Net-(U9-SNS-)") (class "Default")
      (node (ref "C44") (pin "1") (pinfunction "1_1") (pintype "passive"))
      (node (ref "R26") (pin "2") (pinfunction "2_2") (pintype "passive"))
      (node (ref "U9") (pin "15") (pinfunction "SNS-_15") (pintype "passive"))
    )
    (net (code "81") (name "Net-(U9-TGDN)") (class "Default")
      (node (ref "R27") (pin "2") (pinfunction "2_2") (pintype "passive"))
      (node (ref "U9") (pin "11") (pinfunction "TGDN_11") (pintype "passive"))
      (node (ref "U9") (pin "12") (pinfunction "TGUP_12") (pintype "passive"))
    )
    (net (code "82") (name "Net-(U9-VCC)") (class "Default")
      (node (ref "C51") (pin "2") (pinfunction "2_2") (pintype "passive"))
      (node (ref "R33") (pin "1") (pinfunction "1_1") (pintype "passive"))
      (node (ref "U9") (pin "3") (pinfunction "VCC_3") (pintype "passive"))
    )
    (net (code "83") (name "Net-(U9-~{FAULT})") (class "Default")
      (node (ref "R33") (pin "2") (pinfunction "2_2") (pintype "passive"))
      (node (ref "U9") (pin "5") (pinfunction "~{FAULT}_5") (pintype "passive"))
    )
    (net (code "84") (name "Net-(U10-BIAS)") (class "Default")
      (node (ref "R41") (pin "2") (pinfunction "2_2") (pintype "passive"))
      (node (ref "U10") (pin "22") (pinfunction "BIAS_22") (pintype "passive"))
    )
    (net (code "85") (name "Net-(U10-BST)") (class "Default")
      (node (ref "C52") (pin "2") (pinfunction "2_2") (pintype "passive"))
      (node (ref "U10") (pin "20") (pinfunction "BST_20") (pintype "passive"))
    )
    (net (code "86") (name "Net-(U10-EN{slash}UV)") (class "Default")
      (node (ref "R36") (pin "1") (pinfunction "1_1") (pintype "passive"))
      (node (ref "U10") (pin "4") (pinfunction "EN/UV_4") (pintype "passive"))
    )
    (net (code "87") (name "Net-(U10-FB)") (class "Default")
      (node (ref "C65") (pin "2") (pinfunction "2_2") (pintype "passive"))
      (node (ref "R44") (pin "2") (pinfunction "2_2") (pintype "passive"))
      (node (ref "R45") (pin "1") (pinfunction "1_1") (pintype "passive"))
      (node (ref "U10") (pin "24") (pinfunction "FB_24") (pintype "passive"))
    )
    (net (code "88") (name "Net-(U10-INTVCC)") (class "Default")
      (node (ref "C63") (pin "2") (pinfunction "2_2") (pintype "passive"))
      (node (ref "U10") (pin "21") (pinfunction "INTVCC_21") (pintype "passive"))
    )
    (net (code "89") (name "Net-(U10-PG)") (class "Default")
      (node (ref "R42") (pin "2") (pinfunction "2_2") (pintype "passive"))
      (node (ref "U10") (pin "23") (pinfunction "PG_23") (pintype "passive"))
    )
    (net (code "90") (name "Net-(U10-RT)") (class "Default")
      (node (ref "R43") (pin "1") (pinfunction "1_1") (pintype "passive"))
      (node (ref "U10") (pin "3") (pinfunction "RT_3") (pintype "passive"))
    )
    (net (code "91") (name "Net-(U10-TR{slash}SS)") (class "Default")
      (node (ref "C64") (pin "2") (pinfunction "2_2") (pintype "passive"))
      (node (ref "U10") (pin "2") (pinfunction "TR/SS_2") (pintype "passive"))
    )
    (net (code "92") (name "Net-(U11-G)") (class "Default")
      (node (ref "R40") (pin "1") (pinfunction "1_1") (pintype "passive"))
      (node (ref "U11") (pin "4") (pinfunction "G_4") (pintype "passive"))
    )
    (net (code "93") (name "Net-(U12-BST)") (class "Default")
      (node (ref "C62") (pin "2") (pinfunction "2_2") (pintype "passive"))
      (node (ref "U12") (pin "14") (pinfunction "BST_14") (pintype "passive"))
    )
    (net (code "94") (name "Net-(U12-ISET)") (class "Default")
      (node (ref "R47") (pin "2") (pinfunction "2_2") (pintype "passive"))
      (node (ref "U12") (pin "9") (pinfunction "ISET_9") (pintype "passive"))
    )
    (net (code "95") (name "Net-(U12-RUN)") (class "Default")
      (node (ref "C56") (pin "2") (pinfunction "2_2") (pintype "passive"))
      (node (ref "C57") (pin "2") (pinfunction "2_2") (pintype "passive"))
      (node (ref "C58") (pin "2") (pinfunction "2_2") (pintype "passive"))
      (node (ref "C61") (pin "2") (pinfunction "2_2") (pintype "passive"))
      (node (ref "C65") (pin "1") (pinfunction "1_1") (pintype "passive"))
      (node (ref "C66") (pin "2") (pinfunction "2_2") (pintype "passive"))
      (node (ref "L4") (pin "2") (pinfunction "2_2") (pintype "passive"))
      (node (ref "R35") (pin "2") (pinfunction "2_2") (pintype "passive"))
      (node (ref "R37") (pin "2") (pinfunction "2_2") (pintype "passive"))
      (node (ref "R41") (pin "1") (pinfunction "1_1") (pintype "passive"))
      (node (ref "R42") (pin "1") (pinfunction "1_1") (pintype "passive"))
      (node (ref "R44") (pin "1") (pinfunction "1_1") (pintype "passive"))
      (node (ref "U12") (pin "1") (pinfunction "RUN_1") (pintype "passive"))
      (node (ref "U12") (pin "16") (pinfunction "SNS+_16") (pintype "passive"))
      (node (ref "U12") (pin "2") (pinfunction "VIN_2") (pintype "passive"))
    )
    (net (code "96") (name "Net-(U12-SNS-)") (class "Default")
      (node (ref "C61") (pin "1") (pinfunction "1_1") (pintype "passive"))
      (node (ref "R39") (pin "2") (pinfunction "2_2") (pintype "passive"))
      (node (ref "U12") (pin "15") (pinfunction "SNS-_15") (pintype "passive"))
    )
    (net (code "97") (name "Net-(U12-TGDN)") (class "Default")
      (node (ref "R40") (pin "2") (pinfunction "2_2") (pintype "passive"))
      (node (ref "U12") (pin "11") (pinfunction "TGDN_11") (pintype "passive"))
      (node (ref "U12") (pin "12") (pinfunction "TGUP_12") (pintype "passive"))
    )
    (net (code "98") (name "Net-(U12-VCC)") (class "Default")
      (node (ref "C68") (pin "2") (pinfunction "2_2") (pintype "passive"))
      (node (ref "R46") (pin "1") (pinfunction "1_1") (pintype "passive"))
      (node (ref "U12") (pin "3") (pinfunction "VCC_3") (pintype "passive"))
    )
    (net (code "99") (name "Net-(U12-~{FAULT})") (class "Default")
      (node (ref "R46") (pin "2") (pinfunction "2_2") (pintype "passive"))
      (node (ref "U12") (pin "5") (pinfunction "~{FAULT}_5") (pintype "passive"))
    )
    (net (code "100") (name "Net-(U13-BIAS)") (class "Default")
      (node (ref "R54") (pin "2") (pinfunction "2_2") (pintype "passive"))
      (node (ref "U13") (pin "22") (pinfunction "BIAS_22") (pintype "passive"))
    )
    (net (code "101") (name "Net-(U13-BST)") (class "Default")
      (node (ref "C69") (pin "2") (pinfunction "2_2") (pintype "passive"))
      (node (ref "U13") (pin "20") (pinfunction "BST_20") (pintype "passive"))
    )
    (net (code "102") (name "Net-(U13-EN{slash}UV)") (class "Default")
      (node (ref "R49") (pin "1") (pinfunction "1_1") (pintype "passive"))
      (node (ref "U13") (pin "4") (pinfunction "EN/UV_4") (pintype "passive"))
    )
    (net (code "103") (name "Net-(U13-FB)") (class "Default")
      (node (ref "C82") (pin "2") (pinfunction "2_2") (pintype "passive"))
      (node (ref "R57") (pin "2") (pinfunction "2_2") (pintype "passive"))
      (node (ref "R58") (pin "1") (pinfunction "1_1") (pintype "passive"))
      (node (ref "U13") (pin "24") (pinfunction "FB_24") (pintype "passive"))
    )
    (net (code "104") (name "Net-(U13-INTVCC)") (class "Default")
      (node (ref "C80") (pin "2") (pinfunction "2_2") (pintype "passive"))
      (node (ref "U13") (pin "21") (pinfunction "INTVCC_21") (pintype "passive"))
    )
    (net (code "105") (name "Net-(U13-PG)") (class "Default")
      (node (ref "R55") (pin "2") (pinfunction "2_2") (pintype "passive"))
      (node (ref "U13") (pin "23") (pinfunction "PG_23") (pintype "passive"))
    )
    (net (code "106") (name "Net-(U13-RT)") (class "Default")
      (node (ref "R56") (pin "1") (pinfunction "1_1") (pintype "passive"))
      (node (ref "U13") (pin "3") (pinfunction "RT_3") (pintype "passive"))
    )
    (net (code "107") (name "Net-(U13-TR{slash}SS)") (class "Default")
      (node (ref "C81") (pin "2") (pinfunction "2_2") (pintype "passive"))
      (node (ref "U13") (pin "2") (pinfunction "TR/SS_2") (pintype "passive"))
    )
    (net (code "108") (name "Net-(U14-G)") (class "Default")
      (node (ref "R53") (pin "1") (pinfunction "1_1") (pintype "passive"))
      (node (ref "U14") (pin "4") (pinfunction "G_4") (pintype "passive"))
    )
    (net (code "109") (name "Net-(U15-BST)") (class "Default")
      (node (ref "C79") (pin "2") (pinfunction "2_2") (pintype "passive"))
      (node (ref "U15") (pin "14") (pinfunction "BST_14") (pintype "passive"))
    )
    (net (code "110") (name "Net-(U15-ISET)") (class "Default")
      (node (ref "R60") (pin "2") (pinfunction "2_2") (pintype "passive"))
      (node (ref "U15") (pin "9") (pinfunction "ISET_9") (pintype "passive"))
    )
    (net (code "111") (name "Net-(U15-RUN)") (class "Default")
      (node (ref "C73") (pin "2") (pinfunction "2_2") (pintype "passive"))
      (node (ref "C74") (pin "2") (pinfunction "2_2") (pintype "passive"))
      (node (ref "C75") (pin "2") (pinfunction "2_2") (pintype "passive"))
      (node (ref "C78") (pin "2") (pinfunction "2_2") (pintype "passive"))
      (node (ref "C82") (pin "1") (pinfunction "1_1") (pintype "passive"))
      (node (ref "C83") (pin "2") (pinfunction "2_2") (pintype "passive"))
      (node (ref "L5") (pin "2") (pinfunction "2_2") (pintype "passive"))
      (node (ref "R48") (pin "2") (pinfunction "2_2") (pintype "passive"))
      (node (ref "R50") (pin "2") (pinfunction "2_2") (pintype "passive"))
      (node (ref "R54") (pin "1") (pinfunction "1_1") (pintype "passive"))
      (node (ref "R55") (pin "1") (pinfunction "1_1") (pintype "passive"))
      (node (ref "R57") (pin "1") (pinfunction "1_1") (pintype "passive"))
      (node (ref "U15") (pin "1") (pinfunction "RUN_1") (pintype "passive"))
      (node (ref "U15") (pin "16") (pinfunction "SNS+_16") (pintype "passive"))
      (node (ref "U15") (pin "2") (pinfunction "VIN_2") (pintype "passive"))
    )
    (net (code "112") (name "Net-(U15-SNS-)") (class "Default")
      (node (ref "C78") (pin "1") (pinfunction "1_1") (pintype "passive"))
      (node (ref "R52") (pin "2") (pinfunction "2_2") (pintype "passive"))
      (node (ref "U15") (pin "15") (pinfunction "SNS-_15") (pintype "passive"))
    )
    (net (code "113") (name "Net-(U15-TGDN)") (class "Default")
      (node (ref "R53") (pin "2") (pinfunction "2_2") (pintype "passive"))
      (node (ref "U15") (pin "11") (pinfunction "TGDN_11") (pintype "passive"))
      (node (ref "U15") (pin "12") (pinfunction "TGUP_12") (pintype "passive"))
    )
    (net (code "114") (name "Net-(U15-VCC)") (class "Default")
      (node (ref "C85") (pin "2") (pinfunction "2_2") (pintype "passive"))
      (node (ref "R59") (pin "1") (pinfunction "1_1") (pintype "passive"))
      (node (ref "U15") (pin "3") (pinfunction "VCC_3") (pintype "passive"))
    )
    (net (code "115") (name "Net-(U15-~{FAULT})") (class "Default")
      (node (ref "R59") (pin "2") (pinfunction "2_2") (pintype "passive"))
      (node (ref "U15") (pin "5") (pinfunction "~{FAULT}_5") (pintype "passive"))
    )
    (net (code "116") (name "Net-(U16-BIAS)") (class "Default")
      (node (ref "R67") (pin "2") (pinfunction "2_2") (pintype "passive"))
      (node (ref "U16") (pin "22") (pinfunction "BIAS_22") (pintype "passive"))
    )
    (net (code "117") (name "Net-(U16-BST)") (class "Default")
      (node (ref "C86") (pin "2") (pinfunction "2_2") (pintype "passive"))
      (node (ref "U16") (pin "20") (pinfunction "BST_20") (pintype "passive"))
    )
    (net (code "118") (name "Net-(U16-EN{slash}UV)") (class "Default")
      (node (ref "R62") (pin "1") (pinfunction "1_1") (pintype "passive"))
      (node (ref "U16") (pin "4") (pinfunction "EN/UV_4") (pintype "passive"))
    )
    (net (code "119") (name "Net-(U16-FB)") (class "Default")
      (node (ref "C99") (pin "2") (pinfunction "2_2") (pintype "passive"))
      (node (ref "R70") (pin "2") (pinfunction "2_2") (pintype "passive"))
      (node (ref "R71") (pin "1") (pinfunction "1_1") (pintype "passive"))
      (node (ref "U16") (pin "24") (pinfunction "FB_24") (pintype "passive"))
    )
    (net (code "120") (name "Net-(U16-INTVCC)") (class "Default")
      (node (ref "C97") (pin "2") (pinfunction "2_2") (pintype "passive"))
      (node (ref "U16") (pin "21") (pinfunction "INTVCC_21") (pintype "passive"))
    )
    (net (code "121") (name "Net-(U16-PG)") (class "Default")
      (node (ref "R68") (pin "2") (pinfunction "2_2") (pintype "passive"))
      (node (ref "U16") (pin "23") (pinfunction "PG_23") (pintype "passive"))
    )
    (net (code "122") (name "Net-(U16-RT)") (class "Default")
      (node (ref "R69") (pin "1") (pinfunction "1_1") (pintype "passive"))
      (node (ref "U16") (pin "3") (pinfunction "RT_3") (pintype "passive"))
    )
    (net (code "123") (name "Net-(U16-TR{slash}SS)") (class "Default")
      (node (ref "C98") (pin "2") (pinfunction "2_2") (pintype "passive"))
      (node (ref "U16") (pin "2") (pinfunction "TR/SS_2") (pintype "passive"))
    )
    (net (code "124") (name "Net-(U17-G)") (class "Default")
      (node (ref "R66") (pin "1") (pinfunction "1_1") (pintype "passive"))
      (node (ref "U17") (pin "4") (pinfunction "G_4") (pintype "passive"))
    )
    (net (code "125") (name "Net-(U18-BST)") (class "Default")
      (node (ref "C96") (pin "2") (pinfunction "2_2") (pintype "passive"))
      (node (ref "U18") (pin "14") (pinfunction "BST_14") (pintype "passive"))
    )
    (net (code "126") (name "Net-(U18-ISET)") (class "Default")
      (node (ref "R73") (pin "2") (pinfunction "2_2") (pintype "passive"))
      (node (ref "U18") (pin "9") (pinfunction "ISET_9") (pintype "passive"))
    )
    (net (code "127") (name "Net-(U18-RUN)") (class "Default")
      (node (ref "C100") (pin "2") (pinfunction "2_2") (pintype "passive"))
      (node (ref "C90") (pin "2") (pinfunction "2_2") (pintype "passive"))
      (node (ref "C91") (pin "2") (pinfunction "2_2") (pintype "passive"))
      (node (ref "C92") (pin "2") (pinfunction "2_2") (pintype "passive"))
      (node (ref "C95") (pin "2") (pinfunction "2_2") (pintype "passive"))
      (node (ref "C99") (pin "1") (pinfunction "1_1") (pintype "passive"))
      (node (ref "L6") (pin "2") (pinfunction "2_2") (pintype "passive"))
      (node (ref "R61") (pin "2") (pinfunction "2_2") (pintype "passive"))
      (node (ref "R63") (pin "2") (pinfunction "2_2") (pintype "passive"))
      (node (ref "R67") (pin "1") (pinfunction "1_1") (pintype "passive"))
      (node (ref "R68") (pin "1") (pinfunction "1_1") (pintype "passive"))
      (node (ref "R70") (pin "1") (pinfunction "1_1") (pintype "passive"))
      (node (ref "U18") (pin "1") (pinfunction "RUN_1") (pintype "passive"))
      (node (ref "U18") (pin "16") (pinfunction "SNS+_16") (pintype "passive"))
      (node (ref "U18") (pin "2") (pinfunction "VIN_2") (pintype "passive"))
    )
    (net (code "128") (name "Net-(U18-SNS-)") (class "Default")
      (node (ref "C95") (pin "1") (pinfunction "1_1") (pintype "passive"))
      (node (ref "R65") (pin "2") (pinfunction "2_2") (pintype "passive"))
      (node (ref "U18") (pin "15") (pinfunction "SNS-_15") (pintype "passive"))
    )
    (net (code "129") (name "Net-(U18-TGDN)") (class "Default")
      (node (ref "R66") (pin "2") (pinfunction "2_2") (pintype "passive"))
      (node (ref "U18") (pin "11") (pinfunction "TGDN_11") (pintype "passive"))
      (node (ref "U18") (pin "12") (pinfunction "TGUP_12") (pintype "passive"))
    )
    (net (code "130") (name "Net-(U18-VCC)") (class "Default")
      (node (ref "C102") (pin "2") (pinfunction "2_2") (pintype "passive"))
      (node (ref "R72") (pin "1") (pinfunction "1_1") (pintype "passive"))
      (node (ref "U18") (pin "3") (pinfunction "VCC_3") (pintype "passive"))
    )
    (net (code "131") (name "Net-(U18-~{FAULT})") (class "Default")
      (node (ref "R72") (pin "2") (pinfunction "2_2") (pintype "passive"))
      (node (ref "U18") (pin "5") (pinfunction "~{FAULT}_5") (pintype "passive"))
    )
    (net (code "132") (name "unconnected-(U2-NC-Pad2)") (class "Default")
      (node (ref "U2") (pin "2") (pinfunction "NC_2") (pintype "passive"))
    )
    (net (code "133") (name "unconnected-(U2-NC-Pad3)") (class "Default")
      (node (ref "U2") (pin "3") (pinfunction "NC_3") (pintype "passive"))
    )
  )
)
